# untitled.net
KiCad netlist of a schematic drawn in EAGLE
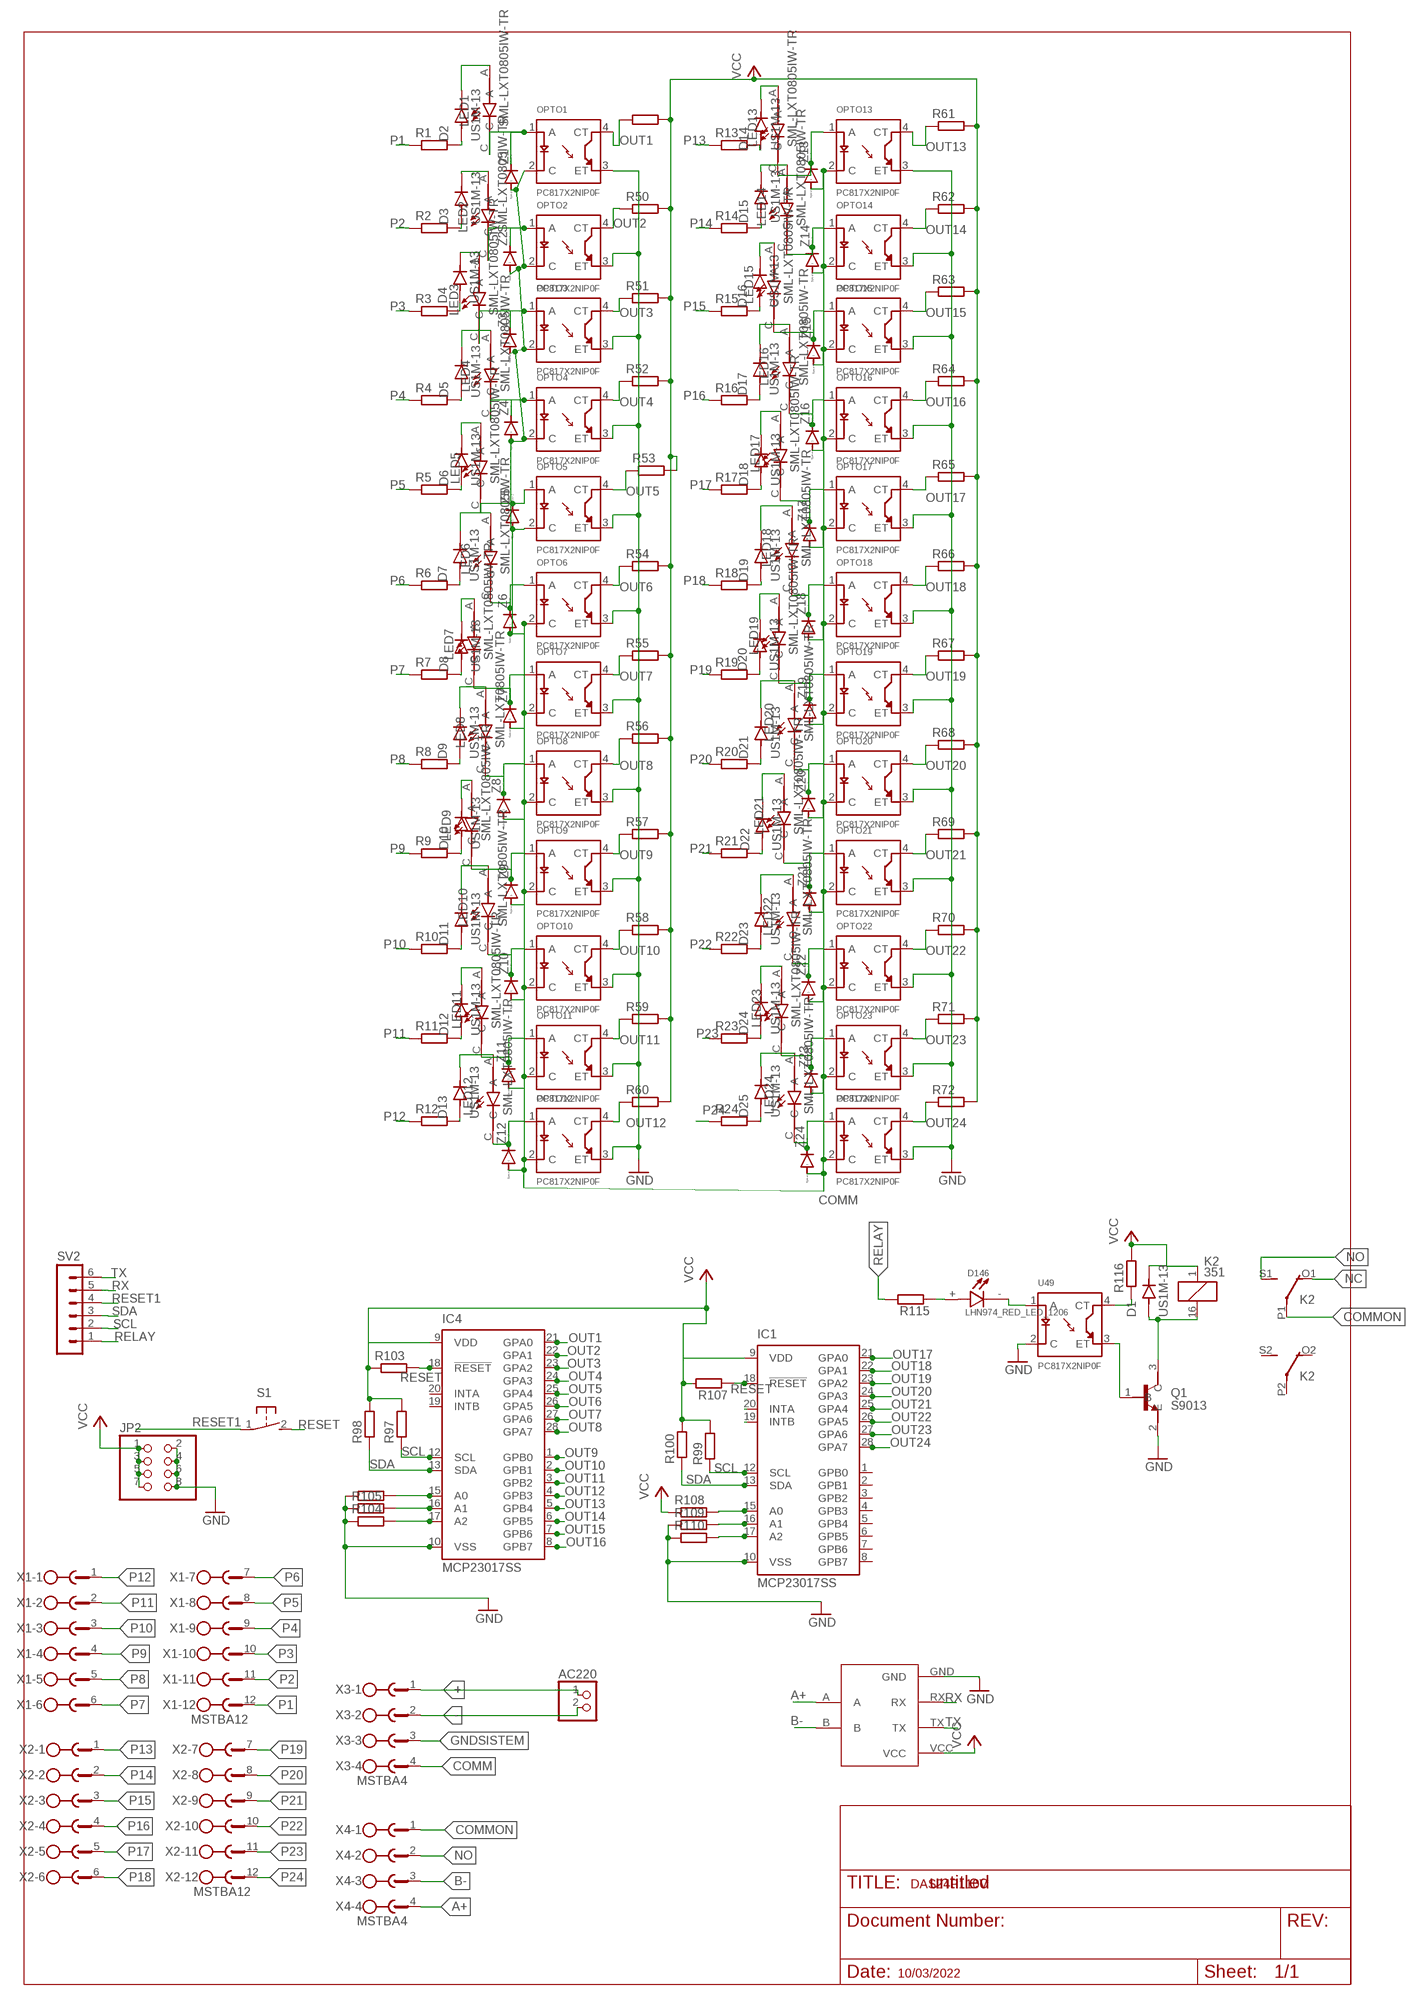
[diagram p0: schematic, sheet 1]

(export (version "E")
  (design (tool "Eeschema 10.0.6"))
  (components
    (comp (ref "AC220")
      (value "PINHD-1X2")
      (footprint "eagle-import:1X02")
      (libsource (lib "eagle-import") (part "PINHD-1X2"))
    )
    (comp (ref "D1")
      (value "US1M-13")
      (footprint "eagle-import:DIOM5226X240N")
      (fields (field (name "MF") "Diodes Incorporated"))
      (libsource (lib "eagle-import") (part "US1M-13"))
    )
    (comp (ref "D2")
      (value "US1M-13")
      (footprint "eagle-import:DIOM5226X240N")
      (fields (field (name "MF") "Diodes Incorporated"))
      (libsource (lib "eagle-import") (part "US1M-13"))
    )
    (comp (ref "D3")
      (value "US1M-13")
      (footprint "eagle-import:DIOM5226X240N")
      (fields (field (name "MF") "Diodes Incorporated"))
      (libsource (lib "eagle-import") (part "US1M-13"))
    )
    (comp (ref "D4")
      (value "US1M-13")
      (footprint "eagle-import:DIOM5226X240N")
      (fields (field (name "MF") "Diodes Incorporated"))
      (libsource (lib "eagle-import") (part "US1M-13"))
    )
    (comp (ref "D5")
      (value "US1M-13")
      (footprint "eagle-import:DIOM5226X240N")
      (fields (field (name "MF") "Diodes Incorporated"))
      (libsource (lib "eagle-import") (part "US1M-13"))
    )
    (comp (ref "D6")
      (value "US1M-13")
      (footprint "eagle-import:DIOM5226X240N")
      (fields (field (name "MF") "Diodes Incorporated"))
      (libsource (lib "eagle-import") (part "US1M-13"))
    )
    (comp (ref "D7")
      (value "US1M-13")
      (footprint "eagle-import:DIOM5226X240N")
      (fields (field (name "MF") "Diodes Incorporated"))
      (libsource (lib "eagle-import") (part "US1M-13"))
    )
    (comp (ref "D8")
      (value "US1M-13")
      (footprint "eagle-import:DIOM5226X240N")
      (fields (field (name "MF") "Diodes Incorporated"))
      (libsource (lib "eagle-import") (part "US1M-13"))
    )
    (comp (ref "D9")
      (value "US1M-13")
      (footprint "eagle-import:DIOM5226X240N")
      (fields (field (name "MF") "Diodes Incorporated"))
      (libsource (lib "eagle-import") (part "US1M-13"))
    )
    (comp (ref "D10")
      (value "US1M-13")
      (footprint "eagle-import:DIOM5226X240N")
      (fields (field (name "MF") "Diodes Incorporated"))
      (libsource (lib "eagle-import") (part "US1M-13"))
    )
    (comp (ref "D11")
      (value "US1M-13")
      (footprint "eagle-import:DIOM5226X240N")
      (fields (field (name "MF") "Diodes Incorporated"))
      (libsource (lib "eagle-import") (part "US1M-13"))
    )
    (comp (ref "D12")
      (value "US1M-13")
      (footprint "eagle-import:DIOM5226X240N")
      (fields (field (name "MF") "Diodes Incorporated"))
      (libsource (lib "eagle-import") (part "US1M-13"))
    )
    (comp (ref "D13")
      (value "US1M-13")
      (footprint "eagle-import:DIOM5226X240N")
      (fields (field (name "MF") "Diodes Incorporated"))
      (libsource (lib "eagle-import") (part "US1M-13"))
    )
    (comp (ref "D14")
      (value "US1M-13")
      (footprint "eagle-import:DIOM5226X240N")
      (fields (field (name "MF") "Diodes Incorporated"))
      (libsource (lib "eagle-import") (part "US1M-13"))
    )
    (comp (ref "D15")
      (value "US1M-13")
      (footprint "eagle-import:DIOM5226X240N")
      (fields (field (name "MF") "Diodes Incorporated"))
      (libsource (lib "eagle-import") (part "US1M-13"))
    )
    (comp (ref "D16")
      (value "US1M-13")
      (footprint "eagle-import:DIOM5226X240N")
      (fields (field (name "MF") "Diodes Incorporated"))
      (libsource (lib "eagle-import") (part "US1M-13"))
    )
    (comp (ref "D17")
      (value "US1M-13")
      (footprint "eagle-import:DIOM5226X240N")
      (fields (field (name "MF") "Diodes Incorporated"))
      (libsource (lib "eagle-import") (part "US1M-13"))
    )
    (comp (ref "D18")
      (value "US1M-13")
      (footprint "eagle-import:DIOM5226X240N")
      (fields (field (name "MF") "Diodes Incorporated"))
      (libsource (lib "eagle-import") (part "US1M-13"))
    )
    (comp (ref "D19")
      (value "US1M-13")
      (footprint "eagle-import:DIOM5226X240N")
      (fields (field (name "MF") "Diodes Incorporated"))
      (libsource (lib "eagle-import") (part "US1M-13"))
    )
    (comp (ref "D20")
      (value "US1M-13")
      (footprint "eagle-import:DIOM5226X240N")
      (fields (field (name "MF") "Diodes Incorporated"))
      (libsource (lib "eagle-import") (part "US1M-13"))
    )
    (comp (ref "D21")
      (value "US1M-13")
      (footprint "eagle-import:DIOM5226X240N")
      (fields (field (name "MF") "Diodes Incorporated"))
      (libsource (lib "eagle-import") (part "US1M-13"))
    )
    (comp (ref "D22")
      (value "US1M-13")
      (footprint "eagle-import:DIOM5226X240N")
      (fields (field (name "MF") "Diodes Incorporated"))
      (libsource (lib "eagle-import") (part "US1M-13"))
    )
    (comp (ref "D23")
      (value "US1M-13")
      (footprint "eagle-import:DIOM5226X240N")
      (fields (field (name "MF") "Diodes Incorporated"))
      (libsource (lib "eagle-import") (part "US1M-13"))
    )
    (comp (ref "D24")
      (value "US1M-13")
      (footprint "eagle-import:DIOM5226X240N")
      (fields (field (name "MF") "Diodes Incorporated"))
      (libsource (lib "eagle-import") (part "US1M-13"))
    )
    (comp (ref "D25")
      (value "US1M-13")
      (footprint "eagle-import:DIOM5226X240N")
      (fields (field (name "MF") "Diodes Incorporated"))
      (libsource (lib "eagle-import") (part "US1M-13"))
    )
    (comp (ref "D146")
      (value "LHN974_RED_LED_1206")
      (footprint "eagle-import:LEDC3216X120N")
      (fields (field (name "MF") "Osram") (field (name "MP") "LHN974 RED LED 1206"))
      (libsource (lib "eagle-import") (part "LHN974_RED_LED_1206"))
    )
    (comp (ref "IC1")
      (value "MCP23017SS")
      (footprint "eagle-import:SSOP28DB")
      (libsource (lib "eagle-import") (part "MCP23017SS"))
    )
    (comp (ref "IC4")
      (value "MCP23017SS")
      (footprint "eagle-import:SSOP28DB")
      (libsource (lib "eagle-import") (part "MCP23017SS"))
    )
    (comp (ref "JP2")
      (value "PINHD-2X4")
      (footprint "eagle-import:2X04")
      (libsource (lib "eagle-import") (part "PINHD-2X4"))
    )
    (comp (ref "K2")
      (value "351")
      (footprint "eagle-import:351")
      (libsource (lib "eagle-import") (part "351"))
    )
    (comp (ref "LED1")
      (value "SML-LXT0805IW-TR")
      (footprint "eagle-import:LEDC2012X120N")
      (fields (field (name "MF") "Lumex Opto/Components"))
      (libsource (lib "eagle-import") (part "SML-LXT0805IW-TR"))
    )
    (comp (ref "LED2")
      (value "SML-LXT0805IW-TR")
      (footprint "eagle-import:LEDC2012X120N")
      (fields (field (name "MF") "Lumex Opto/Components"))
      (libsource (lib "eagle-import") (part "SML-LXT0805IW-TR"))
    )
    (comp (ref "LED3")
      (value "SML-LXT0805IW-TR")
      (footprint "eagle-import:LEDC2012X120N")
      (fields (field (name "MF") "Lumex Opto/Components"))
      (libsource (lib "eagle-import") (part "SML-LXT0805IW-TR"))
    )
    (comp (ref "LED4")
      (value "SML-LXT0805IW-TR")
      (footprint "eagle-import:LEDC2012X120N")
      (fields (field (name "MF") "Lumex Opto/Components"))
      (libsource (lib "eagle-import") (part "SML-LXT0805IW-TR"))
    )
    (comp (ref "LED5")
      (value "SML-LXT0805IW-TR")
      (footprint "eagle-import:LEDC2012X120N")
      (fields (field (name "MF") "Lumex Opto/Components"))
      (libsource (lib "eagle-import") (part "SML-LXT0805IW-TR"))
    )
    (comp (ref "LED6")
      (value "SML-LXT0805IW-TR")
      (footprint "eagle-import:LEDC2012X120N")
      (fields (field (name "MF") "Lumex Opto/Components"))
      (libsource (lib "eagle-import") (part "SML-LXT0805IW-TR"))
    )
    (comp (ref "LED7")
      (value "SML-LXT0805IW-TR")
      (footprint "eagle-import:LEDC2012X120N")
      (fields (field (name "MF") "Lumex Opto/Components"))
      (libsource (lib "eagle-import") (part "SML-LXT0805IW-TR"))
    )
    (comp (ref "LED8")
      (value "SML-LXT0805IW-TR")
      (footprint "eagle-import:LEDC2012X120N")
      (fields (field (name "MF") "Lumex Opto/Components"))
      (libsource (lib "eagle-import") (part "SML-LXT0805IW-TR"))
    )
    (comp (ref "LED9")
      (value "SML-LXT0805IW-TR")
      (footprint "eagle-import:LEDC2012X120N")
      (fields (field (name "MF") "Lumex Opto/Components"))
      (libsource (lib "eagle-import") (part "SML-LXT0805IW-TR"))
    )
    (comp (ref "LED10")
      (value "SML-LXT0805IW-TR")
      (footprint "eagle-import:LEDC2012X120N")
      (fields (field (name "MF") "Lumex Opto/Components"))
      (libsource (lib "eagle-import") (part "SML-LXT0805IW-TR"))
    )
    (comp (ref "LED11")
      (value "SML-LXT0805IW-TR")
      (footprint "eagle-import:LEDC2012X120N")
      (fields (field (name "MF") "Lumex Opto/Components"))
      (libsource (lib "eagle-import") (part "SML-LXT0805IW-TR"))
    )
    (comp (ref "LED12")
      (value "SML-LXT0805IW-TR")
      (footprint "eagle-import:LEDC2012X120N")
      (fields (field (name "MF") "Lumex Opto/Components"))
      (libsource (lib "eagle-import") (part "SML-LXT0805IW-TR"))
    )
    (comp (ref "LED13")
      (value "SML-LXT0805IW-TR")
      (footprint "eagle-import:LEDC2012X120N")
      (fields (field (name "MF") "Lumex Opto/Components"))
      (libsource (lib "eagle-import") (part "SML-LXT0805IW-TR"))
    )
    (comp (ref "LED14")
      (value "SML-LXT0805IW-TR")
      (footprint "eagle-import:LEDC2012X120N")
      (fields (field (name "MF") "Lumex Opto/Components"))
      (libsource (lib "eagle-import") (part "SML-LXT0805IW-TR"))
    )
    (comp (ref "LED15")
      (value "SML-LXT0805IW-TR")
      (footprint "eagle-import:LEDC2012X120N")
      (fields (field (name "MF") "Lumex Opto/Components"))
      (libsource (lib "eagle-import") (part "SML-LXT0805IW-TR"))
    )
    (comp (ref "LED16")
      (value "SML-LXT0805IW-TR")
      (footprint "eagle-import:LEDC2012X120N")
      (fields (field (name "MF") "Lumex Opto/Components"))
      (libsource (lib "eagle-import") (part "SML-LXT0805IW-TR"))
    )
    (comp (ref "LED17")
      (value "SML-LXT0805IW-TR")
      (footprint "eagle-import:LEDC2012X120N")
      (fields (field (name "MF") "Lumex Opto/Components"))
      (libsource (lib "eagle-import") (part "SML-LXT0805IW-TR"))
    )
    (comp (ref "LED18")
      (value "SML-LXT0805IW-TR")
      (footprint "eagle-import:LEDC2012X120N")
      (fields (field (name "MF") "Lumex Opto/Components"))
      (libsource (lib "eagle-import") (part "SML-LXT0805IW-TR"))
    )
    (comp (ref "LED19")
      (value "SML-LXT0805IW-TR")
      (footprint "eagle-import:LEDC2012X120N")
      (fields (field (name "MF") "Lumex Opto/Components"))
      (libsource (lib "eagle-import") (part "SML-LXT0805IW-TR"))
    )
    (comp (ref "LED20")
      (value "SML-LXT0805IW-TR")
      (footprint "eagle-import:LEDC2012X120N")
      (fields (field (name "MF") "Lumex Opto/Components"))
      (libsource (lib "eagle-import") (part "SML-LXT0805IW-TR"))
    )
    (comp (ref "LED21")
      (value "SML-LXT0805IW-TR")
      (footprint "eagle-import:LEDC2012X120N")
      (fields (field (name "MF") "Lumex Opto/Components"))
      (libsource (lib "eagle-import") (part "SML-LXT0805IW-TR"))
    )
    (comp (ref "LED22")
      (value "SML-LXT0805IW-TR")
      (footprint "eagle-import:LEDC2012X120N")
      (fields (field (name "MF") "Lumex Opto/Components"))
      (libsource (lib "eagle-import") (part "SML-LXT0805IW-TR"))
    )
    (comp (ref "LED23")
      (value "SML-LXT0805IW-TR")
      (footprint "eagle-import:LEDC2012X120N")
      (fields (field (name "MF") "Lumex Opto/Components"))
      (libsource (lib "eagle-import") (part "SML-LXT0805IW-TR"))
    )
    (comp (ref "LED24")
      (value "SML-LXT0805IW-TR")
      (footprint "eagle-import:LEDC2012X120N")
      (fields (field (name "MF") "Lumex Opto/Components"))
      (libsource (lib "eagle-import") (part "SML-LXT0805IW-TR"))
    )
    (comp (ref "OPTO1")
      (value "PC817X2NIP0F")
      (footprint "eagle-import:SOT254P975X400-4N")
      (fields (field (name "MF") "Sharp Microelectronics"))
      (libsource (lib "eagle-import") (part "PC817X2NIP0F"))
    )
    (comp (ref "OPTO2")
      (value "PC817X2NIP0F")
      (footprint "eagle-import:SOT254P975X400-4N")
      (fields (field (name "MF") "Sharp Microelectronics"))
      (libsource (lib "eagle-import") (part "PC817X2NIP0F"))
    )
    (comp (ref "OPTO3")
      (value "PC817X2NIP0F")
      (footprint "eagle-import:SOT254P975X400-4N")
      (fields (field (name "MF") "Sharp Microelectronics"))
      (libsource (lib "eagle-import") (part "PC817X2NIP0F"))
    )
    (comp (ref "OPTO4")
      (value "PC817X2NIP0F")
      (footprint "eagle-import:SOT254P975X400-4N")
      (fields (field (name "MF") "Sharp Microelectronics"))
      (libsource (lib "eagle-import") (part "PC817X2NIP0F"))
    )
    (comp (ref "OPTO5")
      (value "PC817X2NIP0F")
      (footprint "eagle-import:SOT254P975X400-4N")
      (fields (field (name "MF") "Sharp Microelectronics"))
      (libsource (lib "eagle-import") (part "PC817X2NIP0F"))
    )
    (comp (ref "OPTO6")
      (value "PC817X2NIP0F")
      (footprint "eagle-import:SOT254P975X400-4N")
      (fields (field (name "MF") "Sharp Microelectronics"))
      (libsource (lib "eagle-import") (part "PC817X2NIP0F"))
    )
    (comp (ref "OPTO7")
      (value "PC817X2NIP0F")
      (footprint "eagle-import:SOT254P975X400-4N")
      (fields (field (name "MF") "Sharp Microelectronics"))
      (libsource (lib "eagle-import") (part "PC817X2NIP0F"))
    )
    (comp (ref "OPTO8")
      (value "PC817X2NIP0F")
      (footprint "eagle-import:SOT254P975X400-4N")
      (fields (field (name "MF") "Sharp Microelectronics"))
      (libsource (lib "eagle-import") (part "PC817X2NIP0F"))
    )
    (comp (ref "OPTO9")
      (value "PC817X2NIP0F")
      (footprint "eagle-import:SOT254P975X400-4N")
      (fields (field (name "MF") "Sharp Microelectronics"))
      (libsource (lib "eagle-import") (part "PC817X2NIP0F"))
    )
    (comp (ref "OPTO10")
      (value "PC817X2NIP0F")
      (footprint "eagle-import:SOT254P975X400-4N")
      (fields (field (name "MF") "Sharp Microelectronics"))
      (libsource (lib "eagle-import") (part "PC817X2NIP0F"))
    )
    (comp (ref "OPTO11")
      (value "PC817X2NIP0F")
      (footprint "eagle-import:SOT254P975X400-4N")
      (fields (field (name "MF") "Sharp Microelectronics"))
      (libsource (lib "eagle-import") (part "PC817X2NIP0F"))
    )
    (comp (ref "OPTO12")
      (value "PC817X2NIP0F")
      (footprint "eagle-import:SOT254P975X400-4N")
      (fields (field (name "MF") "Sharp Microelectronics"))
      (libsource (lib "eagle-import") (part "PC817X2NIP0F"))
    )
    (comp (ref "OPTO13")
      (value "PC817X2NIP0F")
      (footprint "eagle-import:SOT254P975X400-4N")
      (fields (field (name "MF") "Sharp Microelectronics"))
      (libsource (lib "eagle-import") (part "PC817X2NIP0F"))
    )
    (comp (ref "OPTO14")
      (value "PC817X2NIP0F")
      (footprint "eagle-import:SOT254P975X400-4N")
      (fields (field (name "MF") "Sharp Microelectronics"))
      (libsource (lib "eagle-import") (part "PC817X2NIP0F"))
    )
    (comp (ref "OPTO15")
      (value "PC817X2NIP0F")
      (footprint "eagle-import:SOT254P975X400-4N")
      (fields (field (name "MF") "Sharp Microelectronics"))
      (libsource (lib "eagle-import") (part "PC817X2NIP0F"))
    )
    (comp (ref "OPTO16")
      (value "PC817X2NIP0F")
      (footprint "eagle-import:SOT254P975X400-4N")
      (fields (field (name "MF") "Sharp Microelectronics"))
      (libsource (lib "eagle-import") (part "PC817X2NIP0F"))
    )
    (comp (ref "OPTO17")
      (value "PC817X2NIP0F")
      (footprint "eagle-import:SOT254P975X400-4N")
      (fields (field (name "MF") "Sharp Microelectronics"))
      (libsource (lib "eagle-import") (part "PC817X2NIP0F"))
    )
    (comp (ref "OPTO18")
      (value "PC817X2NIP0F")
      (footprint "eagle-import:SOT254P975X400-4N")
      (fields (field (name "MF") "Sharp Microelectronics"))
      (libsource (lib "eagle-import") (part "PC817X2NIP0F"))
    )
    (comp (ref "OPTO19")
      (value "PC817X2NIP0F")
      (footprint "eagle-import:SOT254P975X400-4N")
      (fields (field (name "MF") "Sharp Microelectronics"))
      (libsource (lib "eagle-import") (part "PC817X2NIP0F"))
    )
    (comp (ref "OPTO20")
      (value "PC817X2NIP0F")
      (footprint "eagle-import:SOT254P975X400-4N")
      (fields (field (name "MF") "Sharp Microelectronics"))
      (libsource (lib "eagle-import") (part "PC817X2NIP0F"))
    )
    (comp (ref "OPTO21")
      (value "PC817X2NIP0F")
      (footprint "eagle-import:SOT254P975X400-4N")
      (fields (field (name "MF") "Sharp Microelectronics"))
      (libsource (lib "eagle-import") (part "PC817X2NIP0F"))
    )
    (comp (ref "OPTO22")
      (value "PC817X2NIP0F")
      (footprint "eagle-import:SOT254P975X400-4N")
      (fields (field (name "MF") "Sharp Microelectronics"))
      (libsource (lib "eagle-import") (part "PC817X2NIP0F"))
    )
    (comp (ref "OPTO23")
      (value "PC817X2NIP0F")
      (footprint "eagle-import:SOT254P975X400-4N")
      (fields (field (name "MF") "Sharp Microelectronics"))
      (libsource (lib "eagle-import") (part "PC817X2NIP0F"))
    )
    (comp (ref "OPTO24")
      (value "PC817X2NIP0F")
      (footprint "eagle-import:SOT254P975X400-4N")
      (fields (field (name "MF") "Sharp Microelectronics"))
      (libsource (lib "eagle-import") (part "PC817X2NIP0F"))
    )
    (comp (ref "Q1")
      (value "S9013")
      (footprint "eagle-import:SOT95P240X120-3N")
      (fields (field (name "MF") "JCET"))
      (libsource (lib "eagle-import") (part "S9013"))
    )
    (comp (ref "R1")
      (value "R-EU_0414/15")
      (footprint "eagle-import:0414_15")
      (libsource (lib "eagle-import") (part "R-EU_0414/15"))
    )
    (comp (ref "R2")
      (value "R-EU_0414/15")
      (footprint "eagle-import:0414_15")
      (libsource (lib "eagle-import") (part "R-EU_0414/15"))
    )
    (comp (ref "R3")
      (value "R-EU_0414/15")
      (footprint "eagle-import:0414_15")
      (libsource (lib "eagle-import") (part "R-EU_0414/15"))
    )
    (comp (ref "R4")
      (value "R-EU_0414/15")
      (footprint "eagle-import:0414_15")
      (libsource (lib "eagle-import") (part "R-EU_0414/15"))
    )
    (comp (ref "R5")
      (value "R-EU_0414/15")
      (footprint "eagle-import:0414_15")
      (libsource (lib "eagle-import") (part "R-EU_0414/15"))
    )
    (comp (ref "R6")
      (value "R-EU_0414/15")
      (footprint "eagle-import:0414_15")
      (libsource (lib "eagle-import") (part "R-EU_0414/15"))
    )
    (comp (ref "R7")
      (value "R-EU_0414/15")
      (footprint "eagle-import:0414_15")
      (libsource (lib "eagle-import") (part "R-EU_0414/15"))
    )
    (comp (ref "R8")
      (value "R-EU_0414/15")
      (footprint "eagle-import:0414_15")
      (libsource (lib "eagle-import") (part "R-EU_0414/15"))
    )
    (comp (ref "R9")
      (value "R-EU_0414/15")
      (footprint "eagle-import:0414_15")
      (libsource (lib "eagle-import") (part "R-EU_0414/15"))
    )
    (comp (ref "R10")
      (value "R-EU_0414/15")
      (footprint "eagle-import:0414_15")
      (libsource (lib "eagle-import") (part "R-EU_0414/15"))
    )
    (comp (ref "R11")
      (value "R-EU_0414/15")
      (footprint "eagle-import:0414_15")
      (libsource (lib "eagle-import") (part "R-EU_0414/15"))
    )
    (comp (ref "R12")
      (value "R-EU_0414/15")
      (footprint "eagle-import:0414_15")
      (libsource (lib "eagle-import") (part "R-EU_0414/15"))
    )
    (comp (ref "R13")
      (value "R-EU_0414/15")
      (footprint "eagle-import:0414_15")
      (libsource (lib "eagle-import") (part "R-EU_0414/15"))
    )
    (comp (ref "R14")
      (value "R-EU_0414/15")
      (footprint "eagle-import:0414_15")
      (libsource (lib "eagle-import") (part "R-EU_0414/15"))
    )
    (comp (ref "R15")
      (value "R-EU_0414/15")
      (footprint "eagle-import:0414_15")
      (libsource (lib "eagle-import") (part "R-EU_0414/15"))
    )
    (comp (ref "R16")
      (value "R-EU_0414/15")
      (footprint "eagle-import:0414_15")
      (libsource (lib "eagle-import") (part "R-EU_0414/15"))
    )
    (comp (ref "R17")
      (value "R-EU_0414/15")
      (footprint "eagle-import:0414_15")
      (libsource (lib "eagle-import") (part "R-EU_0414/15"))
    )
    (comp (ref "R18")
      (value "R-EU_0414/15")
      (footprint "eagle-import:0414_15")
      (libsource (lib "eagle-import") (part "R-EU_0414/15"))
    )
    (comp (ref "R19")
      (value "R-EU_0414/15")
      (footprint "eagle-import:0414_15")
      (libsource (lib "eagle-import") (part "R-EU_0414/15"))
    )
    (comp (ref "R20")
      (value "R-EU_0414/15")
      (footprint "eagle-import:0414_15")
      (libsource (lib "eagle-import") (part "R-EU_0414/15"))
    )
    (comp (ref "R21")
      (value "R-EU_0414/15")
      (footprint "eagle-import:0414_15")
      (libsource (lib "eagle-import") (part "R-EU_0414/15"))
    )
    (comp (ref "R22")
      (value "R-EU_0414/15")
      (footprint "eagle-import:0414_15")
      (libsource (lib "eagle-import") (part "R-EU_0414/15"))
    )
    (comp (ref "R23")
      (value "R-EU_0414/15")
      (footprint "eagle-import:0414_15")
      (libsource (lib "eagle-import") (part "R-EU_0414/15"))
    )
    (comp (ref "R24")
      (value "R-EU_0414/15")
      (footprint "eagle-import:0414_15")
      (libsource (lib "eagle-import") (part "R-EU_0414/15"))
    )
    (comp (ref "R49")
      (value "R-EU_R0805")
      (footprint "eagle-import:R0805")
      (libsource (lib "eagle-import") (part "R-EU_R0805"))
    )
    (comp (ref "R50")
      (value "R-EU_R0805")
      (footprint "eagle-import:R0805")
      (libsource (lib "eagle-import") (part "R-EU_R0805"))
    )
    (comp (ref "R51")
      (value "R-EU_R0805")
      (footprint "eagle-import:R0805")
      (libsource (lib "eagle-import") (part "R-EU_R0805"))
    )
    (comp (ref "R52")
      (value "R-EU_R0805")
      (footprint "eagle-import:R0805")
      (libsource (lib "eagle-import") (part "R-EU_R0805"))
    )
    (comp (ref "R53")
      (value "R-EU_R0805")
      (footprint "eagle-import:R0805")
      (libsource (lib "eagle-import") (part "R-EU_R0805"))
    )
    (comp (ref "R54")
      (value "R-EU_R0805")
      (footprint "eagle-import:R0805")
      (libsource (lib "eagle-import") (part "R-EU_R0805"))
    )
    (comp (ref "R55")
      (value "R-EU_R0805")
      (footprint "eagle-import:R0805")
      (libsource (lib "eagle-import") (part "R-EU_R0805"))
    )
    (comp (ref "R56")
      (value "R-EU_R0805")
      (footprint "eagle-import:R0805")
      (libsource (lib "eagle-import") (part "R-EU_R0805"))
    )
    (comp (ref "R57")
      (value "R-EU_R0805")
      (footprint "eagle-import:R0805")
      (libsource (lib "eagle-import") (part "R-EU_R0805"))
    )
    (comp (ref "R58")
      (value "R-EU_R0805")
      (footprint "eagle-import:R0805")
      (libsource (lib "eagle-import") (part "R-EU_R0805"))
    )
    (comp (ref "R59")
      (value "R-EU_R0805")
      (footprint "eagle-import:R0805")
      (libsource (lib "eagle-import") (part "R-EU_R0805"))
    )
    (comp (ref "R60")
      (value "R-EU_R0805")
      (footprint "eagle-import:R0805")
      (libsource (lib "eagle-import") (part "R-EU_R0805"))
    )
    (comp (ref "R61")
      (value "R-EU_R0805")
      (footprint "eagle-import:R0805")
      (libsource (lib "eagle-import") (part "R-EU_R0805"))
    )
    (comp (ref "R62")
      (value "R-EU_R0805")
      (footprint "eagle-import:R0805")
      (libsource (lib "eagle-import") (part "R-EU_R0805"))
    )
    (comp (ref "R63")
      (value "R-EU_R0805")
      (footprint "eagle-import:R0805")
      (libsource (lib "eagle-import") (part "R-EU_R0805"))
    )
    (comp (ref "R64")
      (value "R-EU_R0805")
      (footprint "eagle-import:R0805")
      (libsource (lib "eagle-import") (part "R-EU_R0805"))
    )
    (comp (ref "R65")
      (value "R-EU_R0805")
      (footprint "eagle-import:R0805")
      (libsource (lib "eagle-import") (part "R-EU_R0805"))
    )
    (comp (ref "R66")
      (value "R-EU_R0805")
      (footprint "eagle-import:R0805")
      (libsource (lib "eagle-import") (part "R-EU_R0805"))
    )
    (comp (ref "R67")
      (value "R-EU_R0805")
      (footprint "eagle-import:R0805")
      (libsource (lib "eagle-import") (part "R-EU_R0805"))
    )
    (comp (ref "R68")
      (value "R-EU_R0805")
      (footprint "eagle-import:R0805")
      (libsource (lib "eagle-import") (part "R-EU_R0805"))
    )
    (comp (ref "R69")
      (value "R-EU_R0805")
      (footprint "eagle-import:R0805")
      (libsource (lib "eagle-import") (part "R-EU_R0805"))
    )
    (comp (ref "R70")
      (value "R-EU_R0805")
      (footprint "eagle-import:R0805")
      (libsource (lib "eagle-import") (part "R-EU_R0805"))
    )
    (comp (ref "R71")
      (value "R-EU_R0805")
      (footprint "eagle-import:R0805")
      (libsource (lib "eagle-import") (part "R-EU_R0805"))
    )
    (comp (ref "R72")
      (value "R-EU_R0805")
      (footprint "eagle-import:R0805")
      (libsource (lib "eagle-import") (part "R-EU_R0805"))
    )
    (comp (ref "R97")
      (value "R-EU_R0805")
      (footprint "eagle-import:R0805")
      (libsource (lib "eagle-import") (part "R-EU_R0805"))
    )
    (comp (ref "R98")
      (value "R-EU_R0805")
      (footprint "eagle-import:R0805")
      (libsource (lib "eagle-import") (part "R-EU_R0805"))
    )
    (comp (ref "R99")
      (value "R-EU_R0805")
      (footprint "eagle-import:R0805")
      (libsource (lib "eagle-import") (part "R-EU_R0805"))
    )
    (comp (ref "R100")
      (value "R-EU_R0805")
      (footprint "eagle-import:R0805")
      (libsource (lib "eagle-import") (part "R-EU_R0805"))
    )
    (comp (ref "R103")
      (value "R-EU_R0805")
      (footprint "eagle-import:R0805")
      (libsource (lib "eagle-import") (part "R-EU_R0805"))
    )
    (comp (ref "R104")
      (value "R-EU_R0805")
      (footprint "eagle-import:R0805")
      (libsource (lib "eagle-import") (part "R-EU_R0805"))
    )
    (comp (ref "R105")
      (value "R-EU_R0805")
      (footprint "eagle-import:R0805")
      (libsource (lib "eagle-import") (part "R-EU_R0805"))
    )
    (comp (ref "R106")
      (value "R-EU_R0805")
      (footprint "eagle-import:R0805")
      (libsource (lib "eagle-import") (part "R-EU_R0805"))
    )
    (comp (ref "R107")
      (value "R-EU_R0805")
      (footprint "eagle-import:R0805")
      (libsource (lib "eagle-import") (part "R-EU_R0805"))
    )
    (comp (ref "R108")
      (value "R-EU_R0805")
      (footprint "eagle-import:R0805")
      (libsource (lib "eagle-import") (part "R-EU_R0805"))
    )
    (comp (ref "R109")
      (value "R-EU_R0805")
      (footprint "eagle-import:R0805")
      (libsource (lib "eagle-import") (part "R-EU_R0805"))
    )
    (comp (ref "R110")
      (value "R-EU_R0805")
      (footprint "eagle-import:R0805")
      (libsource (lib "eagle-import") (part "R-EU_R0805"))
    )
    (comp (ref "R115")
      (value "R-EU_R0805")
      (footprint "eagle-import:R0805")
      (libsource (lib "eagle-import") (part "R-EU_R0805"))
    )
    (comp (ref "R116")
      (value "R-EU_R0805")
      (footprint "eagle-import:R0805")
      (libsource (lib "eagle-import") (part "R-EU_R0805"))
    )
    (comp (ref "S1")
      (value "31-XX")
      (footprint "eagle-import:B3F-31XX")
      (fields (field (name "MPN") "B3F-3100"))
      (libsource (lib "eagle-import") (part "31-XX"))
    )
    (comp (ref "SV2")
      (value "MA06-1")
      (footprint "eagle-import:MA06-1")
      (libsource (lib "eagle-import") (part "MA06-1"))
    )
    (comp (ref "TTL-RS1")
      (value "TTL-RS485")
      (footprint "eagle-import:TTL-RS485")
      (libsource (lib "eagle-import") (part "TTL-RS485"))
    )
    (comp (ref "U49")
      (value "PC817X2NIP0F")
      (footprint "eagle-import:SOT254P975X400-4N")
      (fields (field (name "MF") "Sharp Microelectronics"))
      (libsource (lib "eagle-import") (part "PC817X2NIP0F"))
    )
    (comp (ref "X1")
      (value "MSTBA12")
      (footprint "eagle-import:MSTBA12")
      (fields (field (name "MPN") "1757349"))
      (libsource (lib "eagle-import") (part "MSTBA12"))
    )
    (comp (ref "X2")
      (value "MSTBA12")
      (footprint "eagle-import:MSTBA12")
      (fields (field (name "MPN") "1757349"))
      (libsource (lib "eagle-import") (part "MSTBA12"))
    )
    (comp (ref "X3")
      (value "MSTBA4")
      (footprint "eagle-import:MSTBA4")
      (fields (field (name "MF") "FARNELL") (field (name "MPN") "1757268"))
      (libsource (lib "eagle-import") (part "MSTBA4"))
    )
    (comp (ref "X4")
      (value "MSTBA4")
      (footprint "eagle-import:MSTBA4")
      (fields (field (name "MF") "FARNELL") (field (name "MPN") "1757268"))
      (libsource (lib "eagle-import") (part "MSTBA4"))
    )
    (comp (ref "Z1")
      (value "DIODE-SOD123")
      (footprint "eagle-import:SOD123")
      (libsource (lib "eagle-import") (part "DIODE-SOD123"))
    )
    (comp (ref "Z2")
      (value "DIODE-SOD123")
      (footprint "eagle-import:SOD123")
      (libsource (lib "eagle-import") (part "DIODE-SOD123"))
    )
    (comp (ref "Z3")
      (value "DIODE-SOD123")
      (footprint "eagle-import:SOD123")
      (libsource (lib "eagle-import") (part "DIODE-SOD123"))
    )
    (comp (ref "Z4")
      (value "DIODE-SOD123")
      (footprint "eagle-import:SOD123")
      (libsource (lib "eagle-import") (part "DIODE-SOD123"))
    )
    (comp (ref "Z5")
      (value "DIODE-SOD123")
      (footprint "eagle-import:SOD123")
      (libsource (lib "eagle-import") (part "DIODE-SOD123"))
    )
    (comp (ref "Z6")
      (value "DIODE-SOD123")
      (footprint "eagle-import:SOD123")
      (libsource (lib "eagle-import") (part "DIODE-SOD123"))
    )
    (comp (ref "Z7")
      (value "DIODE-SOD123")
      (footprint "eagle-import:SOD123")
      (libsource (lib "eagle-import") (part "DIODE-SOD123"))
    )
    (comp (ref "Z8")
      (value "DIODE-SOD123")
      (footprint "eagle-import:SOD123")
      (libsource (lib "eagle-import") (part "DIODE-SOD123"))
    )
    (comp (ref "Z9")
      (value "DIODE-SOD123")
      (footprint "eagle-import:SOD123")
      (libsource (lib "eagle-import") (part "DIODE-SOD123"))
    )
    (comp (ref "Z10")
      (value "DIODE-SOD123")
      (footprint "eagle-import:SOD123")
      (libsource (lib "eagle-import") (part "DIODE-SOD123"))
    )
    (comp (ref "Z11")
      (value "DIODE-SOD123")
      (footprint "eagle-import:SOD123")
      (libsource (lib "eagle-import") (part "DIODE-SOD123"))
    )
    (comp (ref "Z12")
      (value "DIODE-SOD123")
      (footprint "eagle-import:SOD123")
      (libsource (lib "eagle-import") (part "DIODE-SOD123"))
    )
    (comp (ref "Z13")
      (value "DIODE-SOD123")
      (footprint "eagle-import:SOD123")
      (libsource (lib "eagle-import") (part "DIODE-SOD123"))
    )
    (comp (ref "Z14")
      (value "DIODE-SOD123")
      (footprint "eagle-import:SOD123")
      (libsource (lib "eagle-import") (part "DIODE-SOD123"))
    )
    (comp (ref "Z15")
      (value "DIODE-SOD123")
      (footprint "eagle-import:SOD123")
      (libsource (lib "eagle-import") (part "DIODE-SOD123"))
    )
    (comp (ref "Z16")
      (value "DIODE-SOD123")
      (footprint "eagle-import:SOD123")
      (libsource (lib "eagle-import") (part "DIODE-SOD123"))
    )
    (comp (ref "Z17")
      (value "DIODE-SOD123")
      (footprint "eagle-import:SOD123")
      (libsource (lib "eagle-import") (part "DIODE-SOD123"))
    )
    (comp (ref "Z18")
      (value "DIODE-SOD123")
      (footprint "eagle-import:SOD123")
      (libsource (lib "eagle-import") (part "DIODE-SOD123"))
    )
    (comp (ref "Z19")
      (value "DIODE-SOD123")
      (footprint "eagle-import:SOD123")
      (libsource (lib "eagle-import") (part "DIODE-SOD123"))
    )
    (comp (ref "Z20")
      (value "DIODE-SOD123")
      (footprint "eagle-import:SOD123")
      (libsource (lib "eagle-import") (part "DIODE-SOD123"))
    )
    (comp (ref "Z21")
      (value "DIODE-SOD123")
      (footprint "eagle-import:SOD123")
      (libsource (lib "eagle-import") (part "DIODE-SOD123"))
    )
    (comp (ref "Z22")
      (value "DIODE-SOD123")
      (footprint "eagle-import:SOD123")
      (libsource (lib "eagle-import") (part "DIODE-SOD123"))
    )
    (comp (ref "Z23")
      (value "DIODE-SOD123")
      (footprint "eagle-import:SOD123")
      (libsource (lib "eagle-import") (part "DIODE-SOD123"))
    )
    (comp (ref "Z24")
      (value "DIODE-SOD123")
      (footprint "eagle-import:SOD123")
      (libsource (lib "eagle-import") (part "DIODE-SOD123"))
    )
  )
  (nets
    (net (code "1") (name "+") (class "Default")
      (node (ref "AC220") (pin "1") (pinfunction "1_1") (pintype "passive"))
      (node (ref "X3") (pin "1") (pinfunction "1_1") (pintype "passive"))
    )
    (net (code "2") (name "-") (class "Default")
      (node (ref "AC220") (pin "2") (pinfunction "2_2") (pintype "passive"))
      (node (ref "X3") (pin "2") (pinfunction "1_2") (pintype "passive"))
    )
    (net (code "3") (name "/OUT1") (class "Default")
      (node (ref "IC4") (pin "21") (pinfunction "GPA0_21") (pintype "bidirectional"))
      (node (ref "OPTO1") (pin "4") (pinfunction "CT_4") (pintype "passive"))
      (node (ref "R49") (pin "1") (pinfunction "1_1") (pintype "passive"))
    )
    (net (code "4") (name "/OUT2") (class "Default")
      (node (ref "IC4") (pin "22") (pinfunction "GPA1_22") (pintype "bidirectional"))
      (node (ref "OPTO2") (pin "4") (pinfunction "CT_4") (pintype "passive"))
      (node (ref "R50") (pin "1") (pinfunction "1_1") (pintype "passive"))
    )
    (net (code "5") (name "/OUT3") (class "Default")
      (node (ref "IC4") (pin "23") (pinfunction "GPA2_23") (pintype "bidirectional"))
      (node (ref "OPTO3") (pin "4") (pinfunction "CT_4") (pintype "passive"))
      (node (ref "R51") (pin "1") (pinfunction "1_1") (pintype "passive"))
    )
    (net (code "6") (name "/OUT4") (class "Default")
      (node (ref "IC4") (pin "24") (pinfunction "GPA3_24") (pintype "bidirectional"))
      (node (ref "OPTO4") (pin "4") (pinfunction "CT_4") (pintype "passive"))
      (node (ref "R52") (pin "1") (pinfunction "1_1") (pintype "passive"))
    )
    (net (code "7") (name "/OUT5") (class "Default")
      (node (ref "IC4") (pin "25") (pinfunction "GPA4_25") (pintype "bidirectional"))
      (node (ref "OPTO5") (pin "4") (pinfunction "CT_4") (pintype "passive"))
      (node (ref "R53") (pin "1") (pinfunction "1_1") (pintype "passive"))
    )
    (net (code "8") (name "/OUT6") (class "Default")
      (node (ref "IC4") (pin "26") (pinfunction "GPA5_26") (pintype "bidirectional"))
      (node (ref "OPTO6") (pin "4") (pinfunction "CT_4") (pintype "passive"))
      (node (ref "R54") (pin "1") (pinfunction "1_1") (pintype "passive"))
    )
    (net (code "9") (name "/OUT7") (class "Default")
      (node (ref "IC4") (pin "27") (pinfunction "GPA6_27") (pintype "bidirectional"))
      (node (ref "OPTO7") (pin "4") (pinfunction "CT_4") (pintype "passive"))
      (node (ref "R55") (pin "1") (pinfunction "1_1") (pintype "passive"))
    )
    (net (code "10") (name "/OUT8") (class "Default")
      (node (ref "IC4") (pin "28") (pinfunction "GPA7_28") (pintype "bidirectional"))
      (node (ref "OPTO8") (pin "4") (pinfunction "CT_4") (pintype "passive"))
      (node (ref "R56") (pin "1") (pinfunction "1_1") (pintype "passive"))
    )
    (net (code "11") (name "/OUT9") (class "Default")
      (node (ref "IC4") (pin "1") (pinfunction "GPB0_1") (pintype "bidirectional"))
      (node (ref "OPTO9") (pin "4") (pinfunction "CT_4") (pintype "passive"))
      (node (ref "R57") (pin "1") (pinfunction "1_1") (pintype "passive"))
    )
    (net (code "12") (name "/OUT10") (class "Default")
      (node (ref "IC4") (pin "2") (pinfunction "GPB1_2") (pintype "bidirectional"))
      (node (ref "OPTO10") (pin "4") (pinfunction "CT_4") (pintype "passive"))
      (node (ref "R58") (pin "1") (pinfunction "1_1") (pintype "passive"))
    )
    (net (code "13") (name "/OUT11") (class "Default")
      (node (ref "IC4") (pin "3") (pinfunction "GPB2_3") (pintype "bidirectional"))
      (node (ref "OPTO11") (pin "4") (pinfunction "CT_4") (pintype "passive"))
      (node (ref "R59") (pin "1") (pinfunction "1_1") (pintype "passive"))
    )
    (net (code "14") (name "/OUT12") (class "Default")
      (node (ref "IC4") (pin "4") (pinfunction "GPB3_4") (pintype "bidirectional"))
      (node (ref "OPTO12") (pin "4") (pinfunction "CT_4") (pintype "passive"))
      (node (ref "R60") (pin "1") (pinfunction "1_1") (pintype "passive"))
    )
    (net (code "15") (name "/OUT13") (class "Default")
      (node (ref "IC4") (pin "5") (pinfunction "GPB4_5") (pintype "bidirectional"))
      (node (ref "OPTO13") (pin "4") (pinfunction "CT_4") (pintype "passive"))
      (node (ref "R61") (pin "1") (pinfunction "1_1") (pintype "passive"))
    )
    (net (code "16") (name "/OUT14") (class "Default")
      (node (ref "IC4") (pin "6") (pinfunction "GPB5_6") (pintype "bidirectional"))
      (node (ref "OPTO14") (pin "4") (pinfunction "CT_4") (pintype "passive"))
      (node (ref "R62") (pin "1") (pinfunction "1_1") (pintype "passive"))
    )
    (net (code "17") (name "/OUT15") (class "Default")
      (node (ref "IC4") (pin "7") (pinfunction "GPB6_7") (pintype "bidirectional"))
      (node (ref "OPTO15") (pin "4") (pinfunction "CT_4") (pintype "passive"))
      (node (ref "R63") (pin "1") (pinfunction "1_1") (pintype "passive"))
    )
    (net (code "18") (name "/OUT16") (class "Default")
      (node (ref "IC4") (pin "8") (pinfunction "GPB7_8") (pintype "bidirectional"))
      (node (ref "OPTO16") (pin "4") (pinfunction "CT_4") (pintype "passive"))
      (node (ref "R64") (pin "1") (pinfunction "1_1") (pintype "passive"))
    )
    (net (code "19") (name "/OUT17") (class "Default")
      (node (ref "IC1") (pin "21") (pinfunction "GPA0_21") (pintype "bidirectional"))
      (node (ref "OPTO17") (pin "4") (pinfunction "CT_4") (pintype "passive"))
      (node (ref "R65") (pin "1") (pinfunction "1_1") (pintype "passive"))
    )
    (net (code "20") (name "/OUT18") (class "Default")
      (node (ref "IC1") (pin "22") (pinfunction "GPA1_22") (pintype "bidirectional"))
      (node (ref "OPTO18") (pin "4") (pinfunction "CT_4") (pintype "passive"))
      (node (ref "R66") (pin "1") (pinfunction "1_1") (pintype "passive"))
    )
    (net (code "21") (name "/OUT19") (class "Default")
      (node (ref "IC1") (pin "23") (pinfunction "GPA2_23") (pintype "bidirectional"))
      (node (ref "OPTO19") (pin "4") (pinfunction "CT_4") (pintype "passive"))
      (node (ref "R67") (pin "1") (pinfunction "1_1") (pintype "passive"))
    )
    (net (code "22") (name "/OUT20") (class "Default")
      (node (ref "IC1") (pin "24") (pinfunction "GPA3_24") (pintype "bidirectional"))
      (node (ref "OPTO20") (pin "4") (pinfunction "CT_4") (pintype "passive"))
      (node (ref "R68") (pin "1") (pinfunction "1_1") (pintype "passive"))
    )
    (net (code "23") (name "/OUT21") (class "Default")
      (node (ref "IC1") (pin "25") (pinfunction "GPA4_25") (pintype "bidirectional"))
      (node (ref "OPTO21") (pin "4") (pinfunction "CT_4") (pintype "passive"))
      (node (ref "R69") (pin "1") (pinfunction "1_1") (pintype "passive"))
    )
    (net (code "24") (name "/OUT22") (class "Default")
      (node (ref "IC1") (pin "26") (pinfunction "GPA5_26") (pintype "bidirectional"))
      (node (ref "OPTO22") (pin "4") (pinfunction "CT_4") (pintype "passive"))
      (node (ref "R70") (pin "1") (pinfunction "1_1") (pintype "passive"))
    )
    (net (code "25") (name "/OUT23") (class "Default")
      (node (ref "IC1") (pin "27") (pinfunction "GPA6_27") (pintype "bidirectional"))
      (node (ref "OPTO23") (pin "4") (pinfunction "CT_4") (pintype "passive"))
      (node (ref "R71") (pin "1") (pinfunction "1_1") (pintype "passive"))
    )
    (net (code "26") (name "/OUT24") (class "Default")
      (node (ref "IC1") (pin "28") (pinfunction "GPA7_28") (pintype "bidirectional"))
      (node (ref "OPTO24") (pin "4") (pinfunction "CT_4") (pintype "passive"))
      (node (ref "R72") (pin "1") (pinfunction "1_1") (pintype "passive"))
    )
    (net (code "27") (name "/RESET") (class "Default")
      (node (ref "IC1") (pin "18") (pinfunction "~{RESET}_18") (pintype "input"))
      (node (ref "IC4") (pin "18") (pinfunction "~{RESET}_18") (pintype "input"))
      (node (ref "R103") (pin "2") (pinfunction "2_2") (pintype "passive"))
      (node (ref "R107") (pin "1") (pinfunction "1_1") (pintype "passive"))
      (node (ref "S1") (pin "2") (pinfunction "S_2") (pintype "passive"))
    )
    (net (code "28") (name "/RESET1") (class "Default")
      (node (ref "S1") (pin "1") (pinfunction "P_1") (pintype "passive"))
      (node (ref "SV2") (pin "4") (pinfunction "4_4") (pintype "passive"))
    )
    (net (code "29") (name "/RX") (class "Default")
      (node (ref "SV2") (pin "5") (pinfunction "5_5") (pintype "passive"))
      (node (ref "TTL-RS1") (pin "RX") (pinfunction "RX_RX") (pintype "bidirectional"))
    )
    (net (code "30") (name "/SCL") (class "Default")
      (node (ref "IC1") (pin "12") (pinfunction "SCL_12") (pintype "input"))
      (node (ref "IC4") (pin "12") (pinfunction "SCL_12") (pintype "input"))
      (node (ref "R97") (pin "1") (pinfunction "1_1") (pintype "passive"))
      (node (ref "R99") (pin "1") (pinfunction "1_1") (pintype "passive"))
      (node (ref "SV2") (pin "2") (pinfunction "2_2") (pintype "passive"))
    )
    (net (code "31") (name "/SDA") (class "Default")
      (node (ref "IC1") (pin "13") (pinfunction "SDA_13") (pintype "bidirectional"))
      (node (ref "IC4") (pin "13") (pinfunction "SDA_13") (pintype "bidirectional"))
      (node (ref "R100") (pin "1") (pinfunction "1_1") (pintype "passive"))
      (node (ref "R98") (pin "1") (pinfunction "1_1") (pintype "passive"))
      (node (ref "SV2") (pin "3") (pinfunction "3_3") (pintype "passive"))
    )
    (net (code "32") (name "/TX") (class "Default")
      (node (ref "SV2") (pin "6") (pinfunction "6_6") (pintype "passive"))
      (node (ref "TTL-RS1") (pin "TX") (pinfunction "TX_TX") (pintype "bidirectional"))
    )
    (net (code "33") (name "A+") (class "Default")
      (node (ref "TTL-RS1") (pin "A") (pinfunction "A_A") (pintype "bidirectional"))
      (node (ref "X4") (pin "4") (pinfunction "1_4") (pintype "passive"))
    )
    (net (code "34") (name "B-") (class "Default")
      (node (ref "TTL-RS1") (pin "B") (pinfunction "B_B") (pintype "bidirectional"))
      (node (ref "X4") (pin "3") (pinfunction "1_3") (pintype "passive"))
    )
    (net (code "35") (name "COMM") (class "Default")
      (node (ref "OPTO1") (pin "2") (pinfunction "C_2") (pintype "passive"))
      (node (ref "OPTO10") (pin "2") (pinfunction "C_2") (pintype "passive"))
      (node (ref "OPTO11") (pin "2") (pinfunction "C_2") (pintype "passive"))
      (node (ref "OPTO12") (pin "2") (pinfunction "C_2") (pintype "passive"))
      (node (ref "OPTO13") (pin "2") (pinfunction "C_2") (pintype "passive"))
      (node (ref "OPTO14") (pin "2") (pinfunction "C_2") (pintype "passive"))
      (node (ref "OPTO15") (pin "2") (pinfunction "C_2") (pintype "passive"))
      (node (ref "OPTO16") (pin "2") (pinfunction "C_2") (pintype "passive"))
      (node (ref "OPTO17") (pin "2") (pinfunction "C_2") (pintype "passive"))
      (node (ref "OPTO18") (pin "2") (pinfunction "C_2") (pintype "passive"))
      (node (ref "OPTO19") (pin "2") (pinfunction "C_2") (pintype "passive"))
      (node (ref "OPTO2") (pin "2") (pinfunction "C_2") (pintype "passive"))
      (node (ref "OPTO20") (pin "2") (pinfunction "C_2") (pintype "passive"))
      (node (ref "OPTO21") (pin "2") (pinfunction "C_2") (pintype "passive"))
      (node (ref "OPTO22") (pin "2") (pinfunction "C_2") (pintype "passive"))
      (node (ref "OPTO23") (pin "2") (pinfunction "C_2") (pintype "passive"))
      (node (ref "OPTO24") (pin "2") (pinfunction "C_2") (pintype "passive"))
      (node (ref "OPTO3") (pin "2") (pinfunction "C_2") (pintype "passive"))
      (node (ref "OPTO4") (pin "2") (pinfunction "C_2") (pintype "passive"))
      (node (ref "OPTO5") (pin "2") (pinfunction "C_2") (pintype "passive"))
      (node (ref "OPTO6") (pin "2") (pinfunction "C_2") (pintype "passive"))
      (node (ref "OPTO7") (pin "2") (pinfunction "C_2") (pintype "passive"))
      (node (ref "OPTO8") (pin "2") (pinfunction "C_2") (pintype "passive"))
      (node (ref "OPTO9") (pin "2") (pinfunction "C_2") (pintype "passive"))
      (node (ref "X3") (pin "4") (pinfunction "1_4") (pintype "passive"))
      (node (ref "Z1") (pin "A") (pinfunction "A_A") (pintype "passive"))
      (node (ref "Z10") (pin "A") (pinfunction "A_A") (pintype "passive"))
      (node (ref "Z11") (pin "A") (pinfunction "A_A") (pintype "passive"))
      (node (ref "Z12") (pin "A") (pinfunction "A_A") (pintype "passive"))
      (node (ref "Z13") (pin "A") (pinfunction "A_A") (pintype "passive"))
      (node (ref "Z14") (pin "A") (pinfunction "A_A") (pintype "passive"))
      (node (ref "Z15") (pin "A") (pinfunction "A_A") (pintype "passive"))
      (node (ref "Z16") (pin "A") (pinfunction "A_A") (pintype "passive"))
      (node (ref "Z17") (pin "A") (pinfunction "A_A") (pintype "passive"))
      (node (ref "Z18") (pin "A") (pinfunction "A_A") (pintype "passive"))
      (node (ref "Z19") (pin "A") (pinfunction "A_A") (pintype "passive"))
      (node (ref "Z2") (pin "A") (pinfunction "A_A") (pintype "passive"))
      (node (ref "Z20") (pin "A") (pinfunction "A_A") (pintype "passive"))
      (node (ref "Z21") (pin "A") (pinfunction "A_A") (pintype "passive"))
      (node (ref "Z22") (pin "A") (pinfunction "A_A") (pintype "passive"))
      (node (ref "Z23") (pin "A") (pinfunction "A_A") (pintype "passive"))
      (node (ref "Z24") (pin "A") (pinfunction "A_A") (pintype "passive"))
      (node (ref "Z3") (pin "A") (pinfunction "A_A") (pintype "passive"))
      (node (ref "Z4") (pin "A") (pinfunction "A_A") (pintype "passive"))
      (node (ref "Z5") (pin "A") (pinfunction "A_A") (pintype "passive"))
      (node (ref "Z6") (pin "A") (pinfunction "A_A") (pintype "passive"))
      (node (ref "Z7") (pin "A") (pinfunction "A_A") (pintype "passive"))
      (node (ref "Z8") (pin "A") (pinfunction "A_A") (pintype "passive"))
      (node (ref "Z9") (pin "A") (pinfunction "A_A") (pintype "passive"))
    )
    (net (code "36") (name "COMMON") (class "Default")
      (node (ref "K2") (pin "P1") (pinfunction "P_P1") (pintype "passive"))
      (node (ref "X4") (pin "1") (pinfunction "1_1") (pintype "passive"))
    )
    (net (code "37") (name "GND") (class "Default")
      (node (ref "IC1") (pin "10") (pinfunction "VSS_10") (pintype "power_in"))
      (node (ref "IC4") (pin "10") (pinfunction "VSS_10") (pintype "power_in"))
      (node (ref "JP2") (pin "2") (pinfunction "2_2") (pintype "passive"))
      (node (ref "JP2") (pin "4") (pinfunction "4_4") (pintype "passive"))
      (node (ref "JP2") (pin "6") (pinfunction "6_6") (pintype "passive"))
      (node (ref "JP2") (pin "8") (pinfunction "8_8") (pintype "passive"))
      (node (ref "OPTO1") (pin "3") (pinfunction "ET_3") (pintype "passive"))
      (node (ref "OPTO10") (pin "3") (pinfunction "ET_3") (pintype "passive"))
      (node (ref "OPTO11") (pin "3") (pinfunction "ET_3") (pintype "passive"))
      (node (ref "OPTO12") (pin "3") (pinfunction "ET_3") (pintype "passive"))
      (node (ref "OPTO13") (pin "3") (pinfunction "ET_3") (pintype "passive"))
      (node (ref "OPTO14") (pin "3") (pinfunction "ET_3") (pintype "passive"))
      (node (ref "OPTO15") (pin "3") (pinfunction "ET_3") (pintype "passive"))
      (node (ref "OPTO16") (pin "3") (pinfunction "ET_3") (pintype "passive"))
      (node (ref "OPTO17") (pin "3") (pinfunction "ET_3") (pintype "passive"))
      (node (ref "OPTO18") (pin "3") (pinfunction "ET_3") (pintype "passive"))
      (node (ref "OPTO19") (pin "3") (pinfunction "ET_3") (pintype "passive"))
      (node (ref "OPTO2") (pin "3") (pinfunction "ET_3") (pintype "passive"))
      (node (ref "OPTO20") (pin "3") (pinfunction "ET_3") (pintype "passive"))
      (node (ref "OPTO21") (pin "3") (pinfunction "ET_3") (pintype "passive"))
      (node (ref "OPTO22") (pin "3") (pinfunction "ET_3") (pintype "passive"))
      (node (ref "OPTO23") (pin "3") (pinfunction "ET_3") (pintype "passive"))
      (node (ref "OPTO24") (pin "3") (pinfunction "ET_3") (pintype "passive"))
      (node (ref "OPTO3") (pin "3") (pinfunction "ET_3") (pintype "passive"))
      (node (ref "OPTO4") (pin "3") (pinfunction "ET_3") (pintype "passive"))
      (node (ref "OPTO5") (pin "3") (pinfunction "ET_3") (pintype "passive"))
      (node (ref "OPTO6") (pin "3") (pinfunction "ET_3") (pintype "passive"))
      (node (ref "OPTO7") (pin "3") (pinfunction "ET_3") (pintype "passive"))
      (node (ref "OPTO8") (pin "3") (pinfunction "ET_3") (pintype "passive"))
      (node (ref "OPTO9") (pin "3") (pinfunction "ET_3") (pintype "passive"))
      (node (ref "Q1") (pin "2") (pinfunction "E_2") (pintype "passive"))
      (node (ref "R104") (pin "1") (pinfunction "1_1") (pintype "passive"))
      (node (ref "R105") (pin "1") (pinfunction "1_1") (pintype "passive"))
      (node (ref "R106") (pin "1") (pinfunction "1_1") (pintype "passive"))
      (node (ref "R109") (pin "1") (pinfunction "1_1") (pintype "passive"))
      (node (ref "R110") (pin "1") (pinfunction "1_1") (pintype "passive"))
      (node (ref "TTL-RS1") (pin "GND") (pinfunction "GND_GND") (pintype "bidirectional"))
      (node (ref "U49") (pin "2") (pinfunction "C_2") (pintype "passive"))
    )
    (net (code "38") (name "GNDSISTEM") (class "Default")
      (node (ref "X3") (pin "3") (pinfunction "1_3") (pintype "passive"))
    )
    (net (code "39") (name "NC") (class "Default")
      (node (ref "K2") (pin "O1") (pinfunction "O_O1") (pintype "passive"))
    )
    (net (code "40") (name "NO") (class "Default")
      (node (ref "K2") (pin "S1") (pinfunction "S_S1") (pintype "passive"))
      (node (ref "X4") (pin "2") (pinfunction "1_2") (pintype "passive"))
    )
    (net (code "41") (name "Net-(D2-K)") (class "Default")
      (node (ref "D2") (pin "C") (pinfunction "K_C") (pintype "passive"))
      (node (ref "LED1") (pin "A") (pinfunction "A_A") (pintype "passive"))
    )
    (net (code "42") (name "Net-(D2-PadA)") (class "Default")
      (node (ref "D2") (pin "A") (pinfunction "A_A") (pintype "passive"))
      (node (ref "R1") (pin "2") (pinfunction "2_2") (pintype "passive"))
    )
    (net (code "43") (name "Net-(D3-K)") (class "Default")
      (node (ref "D3") (pin "C") (pinfunction "K_C") (pintype "passive"))
      (node (ref "LED2") (pin "A") (pinfunction "A_A") (pintype "passive"))
    )
    (net (code "44") (name "Net-(D3-PadA)") (class "Default")
      (node (ref "D3") (pin "A") (pinfunction "A_A") (pintype "passive"))
      (node (ref "R2") (pin "2") (pinfunction "2_2") (pintype "passive"))
    )
    (net (code "45") (name "Net-(D4-K)") (class "Default")
      (node (ref "D4") (pin "C") (pinfunction "K_C") (pintype "passive"))
      (node (ref "LED3") (pin "A") (pinfunction "A_A") (pintype "passive"))
    )
    (net (code "46") (name "Net-(D4-PadA)") (class "Default")
      (node (ref "D4") (pin "A") (pinfunction "A_A") (pintype "passive"))
      (node (ref "R3") (pin "2") (pinfunction "2_2") (pintype "passive"))
    )
    (net (code "47") (name "Net-(D5-K)") (class "Default")
      (node (ref "D5") (pin "C") (pinfunction "K_C") (pintype "passive"))
      (node (ref "LED4") (pin "A") (pinfunction "A_A") (pintype "passive"))
    )
    (net (code "48") (name "Net-(D5-PadA)") (class "Default")
      (node (ref "D5") (pin "A") (pinfunction "A_A") (pintype "passive"))
      (node (ref "R4") (pin "2") (pinfunction "2_2") (pintype "passive"))
    )
    (net (code "49") (name "Net-(D6-K)") (class "Default")
      (node (ref "D6") (pin "C") (pinfunction "K_C") (pintype "passive"))
      (node (ref "LED5") (pin "A") (pinfunction "A_A") (pintype "passive"))
    )
    (net (code "50") (name "Net-(D6-PadA)") (class "Default")
      (node (ref "D6") (pin "A") (pinfunction "A_A") (pintype "passive"))
      (node (ref "R5") (pin "2") (pinfunction "2_2") (pintype "passive"))
    )
    (net (code "51") (name "Net-(D7-K)") (class "Default")
      (node (ref "D7") (pin "C") (pinfunction "K_C") (pintype "passive"))
      (node (ref "LED6") (pin "A") (pinfunction "A_A") (pintype "passive"))
    )
    (net (code "52") (name "Net-(D7-PadA)") (class "Default")
      (node (ref "D7") (pin "A") (pinfunction "A_A") (pintype "passive"))
      (node (ref "R6") (pin "2") (pinfunction "2_2") (pintype "passive"))
    )
    (net (code "53") (name "Net-(D8-K)") (class "Default")
      (node (ref "D8") (pin "C") (pinfunction "K_C") (pintype "passive"))
      (node (ref "LED7") (pin "A") (pinfunction "A_A") (pintype "passive"))
    )
    (net (code "54") (name "Net-(D8-PadA)") (class "Default")
      (node (ref "D8") (pin "A") (pinfunction "A_A") (pintype "passive"))
      (node (ref "R7") (pin "2") (pinfunction "2_2") (pintype "passive"))
    )
    (net (code "55") (name "Net-(D9-K)") (class "Default")
      (node (ref "D9") (pin "C") (pinfunction "K_C") (pintype "passive"))
      (node (ref "LED8") (pin "A") (pinfunction "A_A") (pintype "passive"))
    )
    (net (code "56") (name "Net-(D9-PadA)") (class "Default")
      (node (ref "D9") (pin "A") (pinfunction "A_A") (pintype "passive"))
      (node (ref "R8") (pin "2") (pinfunction "2_2") (pintype "passive"))
    )
    (net (code "57") (name "Net-(D10-K)") (class "Default")
      (node (ref "D10") (pin "C") (pinfunction "K_C") (pintype "passive"))
      (node (ref "LED9") (pin "A") (pinfunction "A_A") (pintype "passive"))
    )
    (net (code "58") (name "Net-(D10-PadA)") (class "Default")
      (node (ref "D10") (pin "A") (pinfunction "A_A") (pintype "passive"))
      (node (ref "R9") (pin "2") (pinfunction "2_2") (pintype "passive"))
    )
    (net (code "59") (name "Net-(D11-K)") (class "Default")
      (node (ref "D11") (pin "C") (pinfunction "K_C") (pintype "passive"))
      (node (ref "LED10") (pin "A") (pinfunction "A_A") (pintype "passive"))
    )
    (net (code "60") (name "Net-(D11-PadA)") (class "Default")
      (node (ref "D11") (pin "A") (pinfunction "A_A") (pintype "passive"))
      (node (ref "R10") (pin "2") (pinfunction "2_2") (pintype "passive"))
    )
    (net (code "61") (name "Net-(D12-K)") (class "Default")
      (node (ref "D12") (pin "C") (pinfunction "K_C") (pintype "passive"))
      (node (ref "LED11") (pin "A") (pinfunction "A_A") (pintype "passive"))
    )
    (net (code "62") (name "Net-(D12-PadA)") (class "Default")
      (node (ref "D12") (pin "A") (pinfunction "A_A") (pintype "passive"))
      (node (ref "R11") (pin "2") (pinfunction "2_2") (pintype "passive"))
    )
    (net (code "63") (name "Net-(D13-K)") (class "Default")
      (node (ref "D13") (pin "C") (pinfunction "K_C") (pintype "passive"))
      (node (ref "LED12") (pin "A") (pinfunction "A_A") (pintype "passive"))
    )
    (net (code "64") (name "Net-(D13-PadA)") (class "Default")
      (node (ref "D13") (pin "A") (pinfunction "A_A") (pintype "passive"))
      (node (ref "R12") (pin "2") (pinfunction "2_2") (pintype "passive"))
    )
    (net (code "65") (name "Net-(D14-K)") (class "Default")
      (node (ref "D14") (pin "C") (pinfunction "K_C") (pintype "passive"))
      (node (ref "LED13") (pin "A") (pinfunction "A_A") (pintype "passive"))
    )
    (net (code "66") (name "Net-(D14-PadA)") (class "Default")
      (node (ref "D14") (pin "A") (pinfunction "A_A") (pintype "passive"))
      (node (ref "R13") (pin "2") (pinfunction "2_2") (pintype "passive"))
    )
    (net (code "67") (name "Net-(D15-K)") (class "Default")
      (node (ref "D15") (pin "C") (pinfunction "K_C") (pintype "passive"))
      (node (ref "LED14") (pin "A") (pinfunction "A_A") (pintype "passive"))
    )
    (net (code "68") (name "Net-(D15-PadA)") (class "Default")
      (node (ref "D15") (pin "A") (pinfunction "A_A") (pintype "passive"))
      (node (ref "R14") (pin "2") (pinfunction "2_2") (pintype "passive"))
    )
    (net (code "69") (name "Net-(D16-K)") (class "Default")
      (node (ref "D16") (pin "C") (pinfunction "K_C") (pintype "passive"))
      (node (ref "LED15") (pin "A") (pinfunction "A_A") (pintype "passive"))
    )
    (net (code "70") (name "Net-(D16-PadA)") (class "Default")
      (node (ref "D16") (pin "A") (pinfunction "A_A") (pintype "passive"))
      (node (ref "R15") (pin "2") (pinfunction "2_2") (pintype "passive"))
    )
    (net (code "71") (name "Net-(D17-K)") (class "Default")
      (node (ref "D17") (pin "C") (pinfunction "K_C") (pintype "passive"))
      (node (ref "LED16") (pin "A") (pinfunction "A_A") (pintype "passive"))
    )
    (net (code "72") (name "Net-(D17-PadA)") (class "Default")
      (node (ref "D17") (pin "A") (pinfunction "A_A") (pintype "passive"))
      (node (ref "R16") (pin "2") (pinfunction "2_2") (pintype "passive"))
    )
    (net (code "73") (name "Net-(D18-K)") (class "Default")
      (node (ref "D18") (pin "C") (pinfunction "K_C") (pintype "passive"))
      (node (ref "LED17") (pin "A") (pinfunction "A_A") (pintype "passive"))
    )
    (net (code "74") (name "Net-(D18-PadA)") (class "Default")
      (node (ref "D18") (pin "A") (pinfunction "A_A") (pintype "passive"))
      (node (ref "R17") (pin "2") (pinfunction "2_2") (pintype "passive"))
    )
    (net (code "75") (name "Net-(D19-K)") (class "Default")
      (node (ref "D19") (pin "C") (pinfunction "K_C") (pintype "passive"))
      (node (ref "LED18") (pin "A") (pinfunction "A_A") (pintype "passive"))
    )
    (net (code "76") (name "Net-(D19-PadA)") (class "Default")
      (node (ref "D19") (pin "A") (pinfunction "A_A") (pintype "passive"))
      (node (ref "R18") (pin "2") (pinfunction "2_2") (pintype "passive"))
    )
    (net (code "77") (name "Net-(D20-K)") (class "Default")
      (node (ref "D20") (pin "C") (pinfunction "K_C") (pintype "passive"))
      (node (ref "LED19") (pin "A") (pinfunction "A_A") (pintype "passive"))
    )
    (net (code "78") (name "Net-(D20-PadA)") (class "Default")
      (node (ref "D20") (pin "A") (pinfunction "A_A") (pintype "passive"))
      (node (ref "R19") (pin "2") (pinfunction "2_2") (pintype "passive"))
    )
    (net (code "79") (name "Net-(D21-K)") (class "Default")
      (node (ref "D21") (pin "C") (pinfunction "K_C") (pintype "passive"))
      (node (ref "LED20") (pin "A") (pinfunction "A_A") (pintype "passive"))
    )
    (net (code "80") (name "Net-(D21-PadA)") (class "Default")
      (node (ref "D21") (pin "A") (pinfunction "A_A") (pintype "passive"))
      (node (ref "R20") (pin "2") (pinfunction "2_2") (pintype "passive"))
    )
    (net (code "81") (name "Net-(D22-K)") (class "Default")
      (node (ref "D22") (pin "C") (pinfunction "K_C") (pintype "passive"))
      (node (ref "LED21") (pin "A") (pinfunction "A_A") (pintype "passive"))
    )
    (net (code "82") (name "Net-(D22-PadA)") (class "Default")
      (node (ref "D22") (pin "A") (pinfunction "A_A") (pintype "passive"))
      (node (ref "R21") (pin "2") (pinfunction "2_2") (pintype "passive"))
    )
    (net (code "83") (name "Net-(D23-K)") (class "Default")
      (node (ref "D23") (pin "C") (pinfunction "K_C") (pintype "passive"))
      (node (ref "LED22") (pin "A") (pinfunction "A_A") (pintype "passive"))
    )
    (net (code "84") (name "Net-(D23-PadA)") (class "Default")
      (node (ref "D23") (pin "A") (pinfunction "A_A") (pintype "passive"))
      (node (ref "R22") (pin "2") (pinfunction "2_2") (pintype "passive"))
    )
    (net (code "85") (name "Net-(D24-K)") (class "Default")
      (node (ref "D24") (pin "C") (pinfunction "K_C") (pintype "passive"))
      (node (ref "LED23") (pin "A") (pinfunction "A_A") (pintype "passive"))
    )
    (net (code "86") (name "Net-(D24-PadA)") (class "Default")
      (node (ref "D24") (pin "A") (pinfunction "A_A") (pintype "passive"))
      (node (ref "R23") (pin "2") (pinfunction "2_2") (pintype "passive"))
    )
    (net (code "87") (name "Net-(D25-K)") (class "Default")
      (node (ref "D25") (pin "C") (pinfunction "K_C") (pintype "passive"))
      (node (ref "LED24") (pin "A") (pinfunction "A_A") (pintype "passive"))
    )
    (net (code "88") (name "Net-(D25-PadA)") (class "Default")
      (node (ref "D25") (pin "A") (pinfunction "A_A") (pintype "passive"))
      (node (ref "R24") (pin "2") (pinfunction "2_2") (pintype "passive"))
    )
    (net (code "89") (name "Net-(D146-Pad+)") (class "Default")
      (node (ref "D146") (pin "+") (pinfunction "+_+") (pintype "passive"))
      (node (ref "R115") (pin "1") (pinfunction "1_1") (pintype "passive"))
    )
    (net (code "90") (name "Net-(IC1-A0)") (class "Default")
      (node (ref "IC1") (pin "15") (pinfunction "A0_15") (pintype "input"))
      (node (ref "R108") (pin "2") (pinfunction "2_2") (pintype "passive"))
    )
    (net (code "91") (name "Net-(IC1-A1)") (class "Default")
      (node (ref "IC1") (pin "16") (pinfunction "A1_16") (pintype "input"))
      (node (ref "R109") (pin "2") (pinfunction "2_2") (pintype "passive"))
    )
    (net (code "92") (name "Net-(IC1-A2)") (class "Default")
      (node (ref "IC1") (pin "17") (pinfunction "A2_17") (pintype "input"))
      (node (ref "R110") (pin "2") (pinfunction "2_2") (pintype "passive"))
    )
    (net (code "93") (name "Net-(IC4-A0)") (class "Default")
      (node (ref "IC4") (pin "15") (pinfunction "A0_15") (pintype "input"))
      (node (ref "R106") (pin "2") (pinfunction "2_2") (pintype "passive"))
    )
    (net (code "94") (name "Net-(IC4-A1)") (class "Default")
      (node (ref "IC4") (pin "16") (pinfunction "A1_16") (pintype "input"))
      (node (ref "R105") (pin "2") (pinfunction "2_2") (pintype "passive"))
    )
    (net (code "95") (name "Net-(IC4-A2)") (class "Default")
      (node (ref "IC4") (pin "17") (pinfunction "A2_17") (pintype "input"))
      (node (ref "R104") (pin "2") (pinfunction "2_2") (pintype "passive"))
    )
    (net (code "96") (name "Net-(K2A-2)") (class "Default")
      (node (ref "D1") (pin "A") (pinfunction "A_A") (pintype "passive"))
      (node (ref "K2") (pin "16") (pinfunction "2_16") (pintype "passive"))
      (node (ref "Q1") (pin "3") (pinfunction "C_3") (pintype "passive"))
    )
    (net (code "97") (name "Net-(OPTO1-A)") (class "Default")
      (node (ref "LED1") (pin "C") (pinfunction "C_C") (pintype "passive"))
      (node (ref "OPTO1") (pin "1") (pinfunction "A_1") (pintype "passive"))
      (node (ref "Z1") (pin "C") (pinfunction "C_C") (pintype "passive"))
    )
    (net (code "98") (name "Net-(OPTO2-A)") (class "Default")
      (node (ref "LED2") (pin "C") (pinfunction "C_C") (pintype "passive"))
      (node (ref "OPTO2") (pin "1") (pinfunction "A_1") (pintype "passive"))
      (node (ref "Z2") (pin "C") (pinfunction "C_C") (pintype "passive"))
    )
    (net (code "99") (name "Net-(OPTO3-A)") (class "Default")
      (node (ref "LED3") (pin "C") (pinfunction "C_C") (pintype "passive"))
      (node (ref "OPTO3") (pin "1") (pinfunction "A_1") (pintype "passive"))
      (node (ref "Z3") (pin "C") (pinfunction "C_C") (pintype "passive"))
    )
    (net (code "100") (name "Net-(OPTO4-A)") (class "Default")
      (node (ref "LED4") (pin "C") (pinfunction "C_C") (pintype "passive"))
      (node (ref "OPTO4") (pin "1") (pinfunction "A_1") (pintype "passive"))
      (node (ref "Z4") (pin "C") (pinfunction "C_C") (pintype "passive"))
    )
    (net (code "101") (name "Net-(OPTO5-A)") (class "Default")
      (node (ref "LED5") (pin "C") (pinfunction "C_C") (pintype "passive"))
      (node (ref "OPTO5") (pin "1") (pinfunction "A_1") (pintype "passive"))
      (node (ref "Z5") (pin "C") (pinfunction "C_C") (pintype "passive"))
    )
    (net (code "102") (name "Net-(OPTO6-A)") (class "Default")
      (node (ref "LED6") (pin "C") (pinfunction "C_C") (pintype "passive"))
      (node (ref "OPTO6") (pin "1") (pinfunction "A_1") (pintype "passive"))
      (node (ref "Z6") (pin "C") (pinfunction "C_C") (pintype "passive"))
    )
    (net (code "103") (name "Net-(OPTO7-A)") (class "Default")
      (node (ref "LED7") (pin "C") (pinfunction "C_C") (pintype "passive"))
      (node (ref "OPTO7") (pin "1") (pinfunction "A_1") (pintype "passive"))
      (node (ref "Z7") (pin "C") (pinfunction "C_C") (pintype "passive"))
    )
    (net (code "104") (name "Net-(OPTO8-A)") (class "Default")
      (node (ref "LED8") (pin "C") (pinfunction "C_C") (pintype "passive"))
      (node (ref "OPTO8") (pin "1") (pinfunction "A_1") (pintype "passive"))
      (node (ref "Z8") (pin "C") (pinfunction "C_C") (pintype "passive"))
    )
    (net (code "105") (name "Net-(OPTO9-A)") (class "Default")
      (node (ref "LED9") (pin "C") (pinfunction "C_C") (pintype "passive"))
      (node (ref "OPTO9") (pin "1") (pinfunction "A_1") (pintype "passive"))
      (node (ref "Z9") (pin "C") (pinfunction "C_C") (pintype "passive"))
    )
    (net (code "106") (name "Net-(OPTO10-A)") (class "Default")
      (node (ref "LED10") (pin "C") (pinfunction "C_C") (pintype "passive"))
      (node (ref "OPTO10") (pin "1") (pinfunction "A_1") (pintype "passive"))
      (node (ref "Z10") (pin "C") (pinfunction "C_C") (pintype "passive"))
    )
    (net (code "107") (name "Net-(OPTO11-A)") (class "Default")
      (node (ref "LED11") (pin "C") (pinfunction "C_C") (pintype "passive"))
      (node (ref "OPTO11") (pin "1") (pinfunction "A_1") (pintype "passive"))
      (node (ref "Z11") (pin "C") (pinfunction "C_C") (pintype "passive"))
    )
    (net (code "108") (name "Net-(OPTO12-A)") (class "Default")
      (node (ref "LED12") (pin "C") (pinfunction "C_C") (pintype "passive"))
      (node (ref "OPTO12") (pin "1") (pinfunction "A_1") (pintype "passive"))
      (node (ref "Z12") (pin "C") (pinfunction "C_C") (pintype "passive"))
    )
    (net (code "109") (name "Net-(OPTO13-A)") (class "Default")
      (node (ref "LED13") (pin "C") (pinfunction "C_C") (pintype "passive"))
      (node (ref "OPTO13") (pin "1") (pinfunction "A_1") (pintype "passive"))
      (node (ref "Z13") (pin "C") (pinfunction "C_C") (pintype "passive"))
    )
    (net (code "110") (name "Net-(OPTO14-A)") (class "Default")
      (node (ref "LED14") (pin "C") (pinfunction "C_C") (pintype "passive"))
      (node (ref "OPTO14") (pin "1") (pinfunction "A_1") (pintype "passive"))
      (node (ref "Z14") (pin "C") (pinfunction "C_C") (pintype "passive"))
    )
    (net (code "111") (name "Net-(OPTO15-A)") (class "Default")
      (node (ref "LED15") (pin "C") (pinfunction "C_C") (pintype "passive"))
      (node (ref "OPTO15") (pin "1") (pinfunction "A_1") (pintype "passive"))
      (node (ref "Z15") (pin "C") (pinfunction "C_C") (pintype "passive"))
    )
    (net (code "112") (name "Net-(OPTO16-A)") (class "Default")
      (node (ref "LED16") (pin "C") (pinfunction "C_C") (pintype "passive"))
      (node (ref "OPTO16") (pin "1") (pinfunction "A_1") (pintype "passive"))
      (node (ref "Z16") (pin "C") (pinfunction "C_C") (pintype "passive"))
    )
    (net (code "113") (name "Net-(OPTO17-A)") (class "Default")
      (node (ref "LED17") (pin "C") (pinfunction "C_C") (pintype "passive"))
      (node (ref "OPTO17") (pin "1") (pinfunction "A_1") (pintype "passive"))
      (node (ref "Z17") (pin "C") (pinfunction "C_C") (pintype "passive"))
    )
    (net (code "114") (name "Net-(OPTO18-A)") (class "Default")
      (node (ref "LED18") (pin "C") (pinfunction "C_C") (pintype "passive"))
      (node (ref "OPTO18") (pin "1") (pinfunction "A_1") (pintype "passive"))
      (node (ref "Z18") (pin "C") (pinfunction "C_C") (pintype "passive"))
    )
    (net (code "115") (name "Net-(OPTO19-A)") (class "Default")
      (node (ref "LED19") (pin "C") (pinfunction "C_C") (pintype "passive"))
      (node (ref "OPTO19") (pin "1") (pinfunction "A_1") (pintype "passive"))
      (node (ref "Z19") (pin "C") (pinfunction "C_C") (pintype "passive"))
    )
    (net (code "116") (name "Net-(OPTO20-A)") (class "Default")
      (node (ref "LED20") (pin "C") (pinfunction "C_C") (pintype "passive"))
      (node (ref "OPTO20") (pin "1") (pinfunction "A_1") (pintype "passive"))
      (node (ref "Z20") (pin "C") (pinfunction "C_C") (pintype "passive"))
    )
    (net (code "117") (name "Net-(OPTO21-A)") (class "Default")
      (node (ref "LED21") (pin "C") (pinfunction "C_C") (pintype "passive"))
      (node (ref "OPTO21") (pin "1") (pinfunction "A_1") (pintype "passive"))
      (node (ref "Z21") (pin "C") (pinfunction "C_C") (pintype "passive"))
    )
    (net (code "118") (name "Net-(OPTO22-A)") (class "Default")
      (node (ref "LED22") (pin "C") (pinfunction "C_C") (pintype "passive"))
      (node (ref "OPTO22") (pin "1") (pinfunction "A_1") (pintype "passive"))
      (node (ref "Z22") (pin "C") (pinfunction "C_C") (pintype "passive"))
    )
    (net (code "119") (name "Net-(OPTO23-A)") (class "Default")
      (node (ref "LED23") (pin "C") (pinfunction "C_C") (pintype "passive"))
      (node (ref "OPTO23") (pin "1") (pinfunction "A_1") (pintype "passive"))
      (node (ref "Z23") (pin "C") (pinfunction "C_C") (pintype "passive"))
    )
    (net (code "120") (name "Net-(OPTO24-A)") (class "Default")
      (node (ref "LED24") (pin "C") (pinfunction "C_C") (pintype "passive"))
      (node (ref "OPTO24") (pin "1") (pinfunction "A_1") (pintype "passive"))
      (node (ref "Z24") (pin "C") (pinfunction "C_C") (pintype "passive"))
    )
    (net (code "121") (name "Net-(Q1-B)") (class "Default")
      (node (ref "Q1") (pin "1") (pinfunction "B_1") (pintype "passive"))
      (node (ref "U49") (pin "3") (pinfunction "ET_3") (pintype "passive"))
    )
    (net (code "122") (name "Net-(U49-A)") (class "Default")
      (node (ref "D146") (pin "-") (pinfunction "-_-") (pintype "passive"))
      (node (ref "U49") (pin "1") (pinfunction "A_1") (pintype "passive"))
    )
    (net (code "123") (name "Net-(U49-CT)") (class "Default")
      (node (ref "R116") (pin "1") (pinfunction "1_1") (pintype "passive"))
      (node (ref "U49") (pin "4") (pinfunction "CT_4") (pintype "passive"))
    )
    (net (code "124") (name "P1") (class "Default")
      (node (ref "R1") (pin "1") (pinfunction "1_1") (pintype "passive"))
      (node (ref "X1") (pin "12") (pinfunction "1_12") (pintype "passive"))
    )
    (net (code "125") (name "P2") (class "Default")
      (node (ref "R2") (pin "1") (pinfunction "1_1") (pintype "passive"))
      (node (ref "X1") (pin "11") (pinfunction "1_11") (pintype "passive"))
    )
    (net (code "126") (name "P3") (class "Default")
      (node (ref "R3") (pin "1") (pinfunction "1_1") (pintype "passive"))
      (node (ref "X1") (pin "10") (pinfunction "1_10") (pintype "passive"))
    )
    (net (code "127") (name "P4") (class "Default")
      (node (ref "R4") (pin "1") (pinfunction "1_1") (pintype "passive"))
      (node (ref "X1") (pin "9") (pinfunction "1_9") (pintype "passive"))
    )
    (net (code "128") (name "P5") (class "Default")
      (node (ref "R5") (pin "1") (pinfunction "1_1") (pintype "passive"))
      (node (ref "X1") (pin "8") (pinfunction "1_8") (pintype "passive"))
    )
    (net (code "129") (name "P6") (class "Default")
      (node (ref "R6") (pin "1") (pinfunction "1_1") (pintype "passive"))
      (node (ref "X1") (pin "7") (pinfunction "1_7") (pintype "passive"))
    )
    (net (code "130") (name "P7") (class "Default")
      (node (ref "R7") (pin "1") (pinfunction "1_1") (pintype "passive"))
      (node (ref "X1") (pin "6") (pinfunction "1_6") (pintype "passive"))
    )
    (net (code "131") (name "P8") (class "Default")
      (node (ref "R8") (pin "1") (pinfunction "1_1") (pintype "passive"))
      (node (ref "X1") (pin "5") (pinfunction "1_5") (pintype "passive"))
    )
    (net (code "132") (name "P9") (class "Default")
      (node (ref "R9") (pin "1") (pinfunction "1_1") (pintype "passive"))
      (node (ref "X1") (pin "4") (pinfunction "1_4") (pintype "passive"))
    )
    (net (code "133") (name "P10") (class "Default")
      (node (ref "R10") (pin "1") (pinfunction "1_1") (pintype "passive"))
      (node (ref "X1") (pin "3") (pinfunction "1_3") (pintype "passive"))
    )
    (net (code "134") (name "P11") (class "Default")
      (node (ref "R11") (pin "1") (pinfunction "1_1") (pintype "passive"))
      (node (ref "X1") (pin "2") (pinfunction "1_2") (pintype "passive"))
    )
    (net (code "135") (name "P12") (class "Default")
      (node (ref "R12") (pin "1") (pinfunction "1_1") (pintype "passive"))
      (node (ref "X1") (pin "1") (pinfunction "1_1") (pintype "passive"))
    )
    (net (code "136") (name "P13") (class "Default")
      (node (ref "R13") (pin "1") (pinfunction "1_1") (pintype "passive"))
      (node (ref "X2") (pin "1") (pinfunction "1_1") (pintype "passive"))
    )
    (net (code "137") (name "P14") (class "Default")
      (node (ref "R14") (pin "1") (pinfunction "1_1") (pintype "passive"))
      (node (ref "X2") (pin "2") (pinfunction "1_2") (pintype "passive"))
    )
    (net (code "138") (name "P15") (class "Default")
      (node (ref "R15") (pin "1") (pinfunction "1_1") (pintype "passive"))
      (node (ref "X2") (pin "3") (pinfunction "1_3") (pintype "passive"))
    )
    (net (code "139") (name "P16") (class "Default")
      (node (ref "R16") (pin "1") (pinfunction "1_1") (pintype "passive"))
      (node (ref "X2") (pin "4") (pinfunction "1_4") (pintype "passive"))
    )
    (net (code "140") (name "P17") (class "Default")
      (node (ref "R17") (pin "1") (pinfunction "1_1") (pintype "passive"))
      (node (ref "X2") (pin "5") (pinfunction "1_5") (pintype "passive"))
    )
    (net (code "141") (name "P18") (class "Default")
      (node (ref "R18") (pin "1") (pinfunction "1_1") (pintype "passive"))
      (node (ref "X2") (pin "6") (pinfunction "1_6") (pintype "passive"))
    )
    (net (code "142") (name "P19") (class "Default")
      (node (ref "R19") (pin "1") (pinfunction "1_1") (pintype "passive"))
      (node (ref "X2") (pin "7") (pinfunction "1_7") (pintype "passive"))
    )
    (net (code "143") (name "P20") (class "Default")
      (node (ref "R20") (pin "1") (pinfunction "1_1") (pintype "passive"))
      (node (ref "X2") (pin "8") (pinfunction "1_8") (pintype "passive"))
    )
    (net (code "144") (name "P21") (class "Default")
      (node (ref "R21") (pin "1") (pinfunction "1_1") (pintype "passive"))
      (node (ref "X2") (pin "9") (pinfunction "1_9") (pintype "passive"))
    )
    (net (code "145") (name "P22") (class "Default")
      (node (ref "R22") (pin "1") (pinfunction "1_1") (pintype "passive"))
      (node (ref "X2") (pin "10") (pinfunction "1_10") (pintype "passive"))
    )
    (net (code "146") (name "P23") (class "Default")
      (node (ref "R23") (pin "1") (pinfunction "1_1") (pintype "passive"))
      (node (ref "X2") (pin "11") (pinfunction "1_11") (pintype "passive"))
    )
    (net (code "147") (name "P24") (class "Default")
      (node (ref "R24") (pin "1") (pinfunction "1_1") (pintype "passive"))
      (node (ref "X2") (pin "12") (pinfunction "1_12") (pintype "passive"))
    )
    (net (code "148") (name "RELAY") (class "Default")
      (node (ref "R115") (pin "2") (pinfunction "2_2") (pintype "passive"))
      (node (ref "SV2") (pin "1") (pinfunction "1_1") (pintype "passive"))
    )
    (net (code "149") (name "VCC") (class "Default")
      (node (ref "D1") (pin "C") (pinfunction "K_C") (pintype "passive"))
      (node (ref "IC1") (pin "9") (pinfunction "VDD_9") (pintype "power_in"))
      (node (ref "IC4") (pin "9") (pinfunction "VDD_9") (pintype "power_in"))
      (node (ref "JP2") (pin "1") (pinfunction "1_1") (pintype "passive"))
      (node (ref "JP2") (pin "3") (pinfunction "3_3") (pintype "passive"))
      (node (ref "JP2") (pin "5") (pinfunction "5_5") (pintype "passive"))
      (node (ref "JP2") (pin "7") (pinfunction "7_7") (pintype "passive"))
      (node (ref "K2") (pin "1") (pinfunction "1_1") (pintype "passive"))
      (node (ref "R100") (pin "2") (pinfunction "2_2") (pintype "passive"))
      (node (ref "R103") (pin "1") (pinfunction "1_1") (pintype "passive"))
      (node (ref "R107") (pin "2") (pinfunction "2_2") (pintype "passive"))
      (node (ref "R108") (pin "1") (pinfunction "1_1") (pintype "passive"))
      (node (ref "R116") (pin "2") (pinfunction "2_2") (pintype "passive"))
      (node (ref "R49") (pin "2") (pinfunction "2_2") (pintype "passive"))
      (node (ref "R50") (pin "2") (pinfunction "2_2") (pintype "passive"))
      (node (ref "R51") (pin "2") (pinfunction "2_2") (pintype "passive"))
      (node (ref "R52") (pin "2") (pinfunction "2_2") (pintype "passive"))
      (node (ref "R53") (pin "2") (pinfunction "2_2") (pintype "passive"))
      (node (ref "R54") (pin "2") (pinfunction "2_2") (pintype "passive"))
      (node (ref "R55") (pin "2") (pinfunction "2_2") (pintype "passive"))
      (node (ref "R56") (pin "2") (pinfunction "2_2") (pintype "passive"))
      (node (ref "R57") (pin "2") (pinfunction "2_2") (pintype "passive"))
      (node (ref "R58") (pin "2") (pinfunction "2_2") (pintype "passive"))
      (node (ref "R59") (pin "2") (pinfunction "2_2") (pintype "passive"))
      (node (ref "R60") (pin "2") (pinfunction "2_2") (pintype "passive"))
      (node (ref "R61") (pin "2") (pinfunction "2_2") (pintype "passive"))
      (node (ref "R62") (pin "2") (pinfunction "2_2") (pintype "passive"))
      (node (ref "R63") (pin "2") (pinfunction "2_2") (pintype "passive"))
      (node (ref "R64") (pin "2") (pinfunction "2_2") (pintype "passive"))
      (node (ref "R65") (pin "2") (pinfunction "2_2") (pintype "passive"))
      (node (ref "R66") (pin "2") (pinfunction "2_2") (pintype "passive"))
      (node (ref "R67") (pin "2") (pinfunction "2_2") (pintype "passive"))
      (node (ref "R68") (pin "2") (pinfunction "2_2") (pintype "passive"))
      (node (ref "R69") (pin "2") (pinfunction "2_2") (pintype "passive"))
      (node (ref "R70") (pin "2") (pinfunction "2_2") (pintype "passive"))
      (node (ref "R71") (pin "2") (pinfunction "2_2") (pintype "passive"))
      (node (ref "R72") (pin "2") (pinfunction "2_2") (pintype "passive"))
      (node (ref "R97") (pin "2") (pinfunction "2_2") (pintype "passive"))
      (node (ref "R98") (pin "2") (pinfunction "2_2") (pintype "passive"))
      (node (ref "R99") (pin "2") (pinfunction "2_2") (pintype "passive"))
      (node (ref "TTL-RS1") (pin "VCC") (pinfunction "VCC_VCC") (pintype "bidirectional"))
    )
    (net (code "150") (name "unconnected-(IC1-GPB0-Pad1)") (class "Default")
      (node (ref "IC1") (pin "1") (pinfunction "GPB0_1") (pintype "bidirectional"))
    )
    (net (code "151") (name "unconnected-(IC1-GPB1-Pad2)") (class "Default")
      (node (ref "IC1") (pin "2") (pinfunction "GPB1_2") (pintype "bidirectional"))
    )
    (net (code "152") (name "unconnected-(IC1-GPB2-Pad3)") (class "Default")
      (node (ref "IC1") (pin "3") (pinfunction "GPB2_3") (pintype "bidirectional"))
    )
    (net (code "153") (name "unconnected-(IC1-GPB3-Pad4)") (class "Default")
      (node (ref "IC1") (pin "4") (pinfunction "GPB3_4") (pintype "bidirectional"))
    )
    (net (code "154") (name "unconnected-(IC1-GPB4-Pad5)") (class "Default")
      (node (ref "IC1") (pin "5") (pinfunction "GPB4_5") (pintype "bidirectional"))
    )
    (net (code "155") (name "unconnected-(IC1-GPB5-Pad6)") (class "Default")
      (node (ref "IC1") (pin "6") (pinfunction "GPB5_6") (pintype "bidirectional"))
    )
    (net (code "156") (name "unconnected-(IC1-GPB6-Pad7)") (class "Default")
      (node (ref "IC1") (pin "7") (pinfunction "GPB6_7") (pintype "bidirectional"))
    )
    (net (code "157") (name "unconnected-(IC1-GPB7-Pad8)") (class "Default")
      (node (ref "IC1") (pin "8") (pinfunction "GPB7_8") (pintype "bidirectional"))
    )
    (net (code "158") (name "unconnected-(IC1-INTA-Pad20)") (class "Default")
      (node (ref "IC1") (pin "20") (pinfunction "INTA_20") (pintype "output"))
    )
    (net (code "159") (name "unconnected-(IC1-INTB-Pad19)") (class "Default")
      (node (ref "IC1") (pin "19") (pinfunction "INTB_19") (pintype "output"))
    )
    (net (code "160") (name "unconnected-(IC4-INTA-Pad20)") (class "Default")
      (node (ref "IC4") (pin "20") (pinfunction "INTA_20") (pintype "output"))
    )
    (net (code "161") (name "unconnected-(IC4-INTB-Pad19)") (class "Default")
      (node (ref "IC4") (pin "19") (pinfunction "INTB_19") (pintype "output"))
    )
    (net (code "162") (name "unconnected-(K2C-O-PadO2)") (class "Default")
      (node (ref "K2") (pin "O2") (pinfunction "O_O2") (pintype "passive"))
    )
    (net (code "163") (name "unconnected-(K2C-P-PadP2)") (class "Default")
      (node (ref "K2") (pin "P2") (pinfunction "P_P2") (pintype "passive"))
    )
    (net (code "164") (name "unconnected-(K2C-S-PadS2)") (class "Default")
      (node (ref "K2") (pin "S2") (pinfunction "S_S2") (pintype "passive"))
    )
  )
)
